# Ideamart_NB-IoT_DevBoard_v1_1.net
KiCad netlist of a schematic drawn in EAGLE
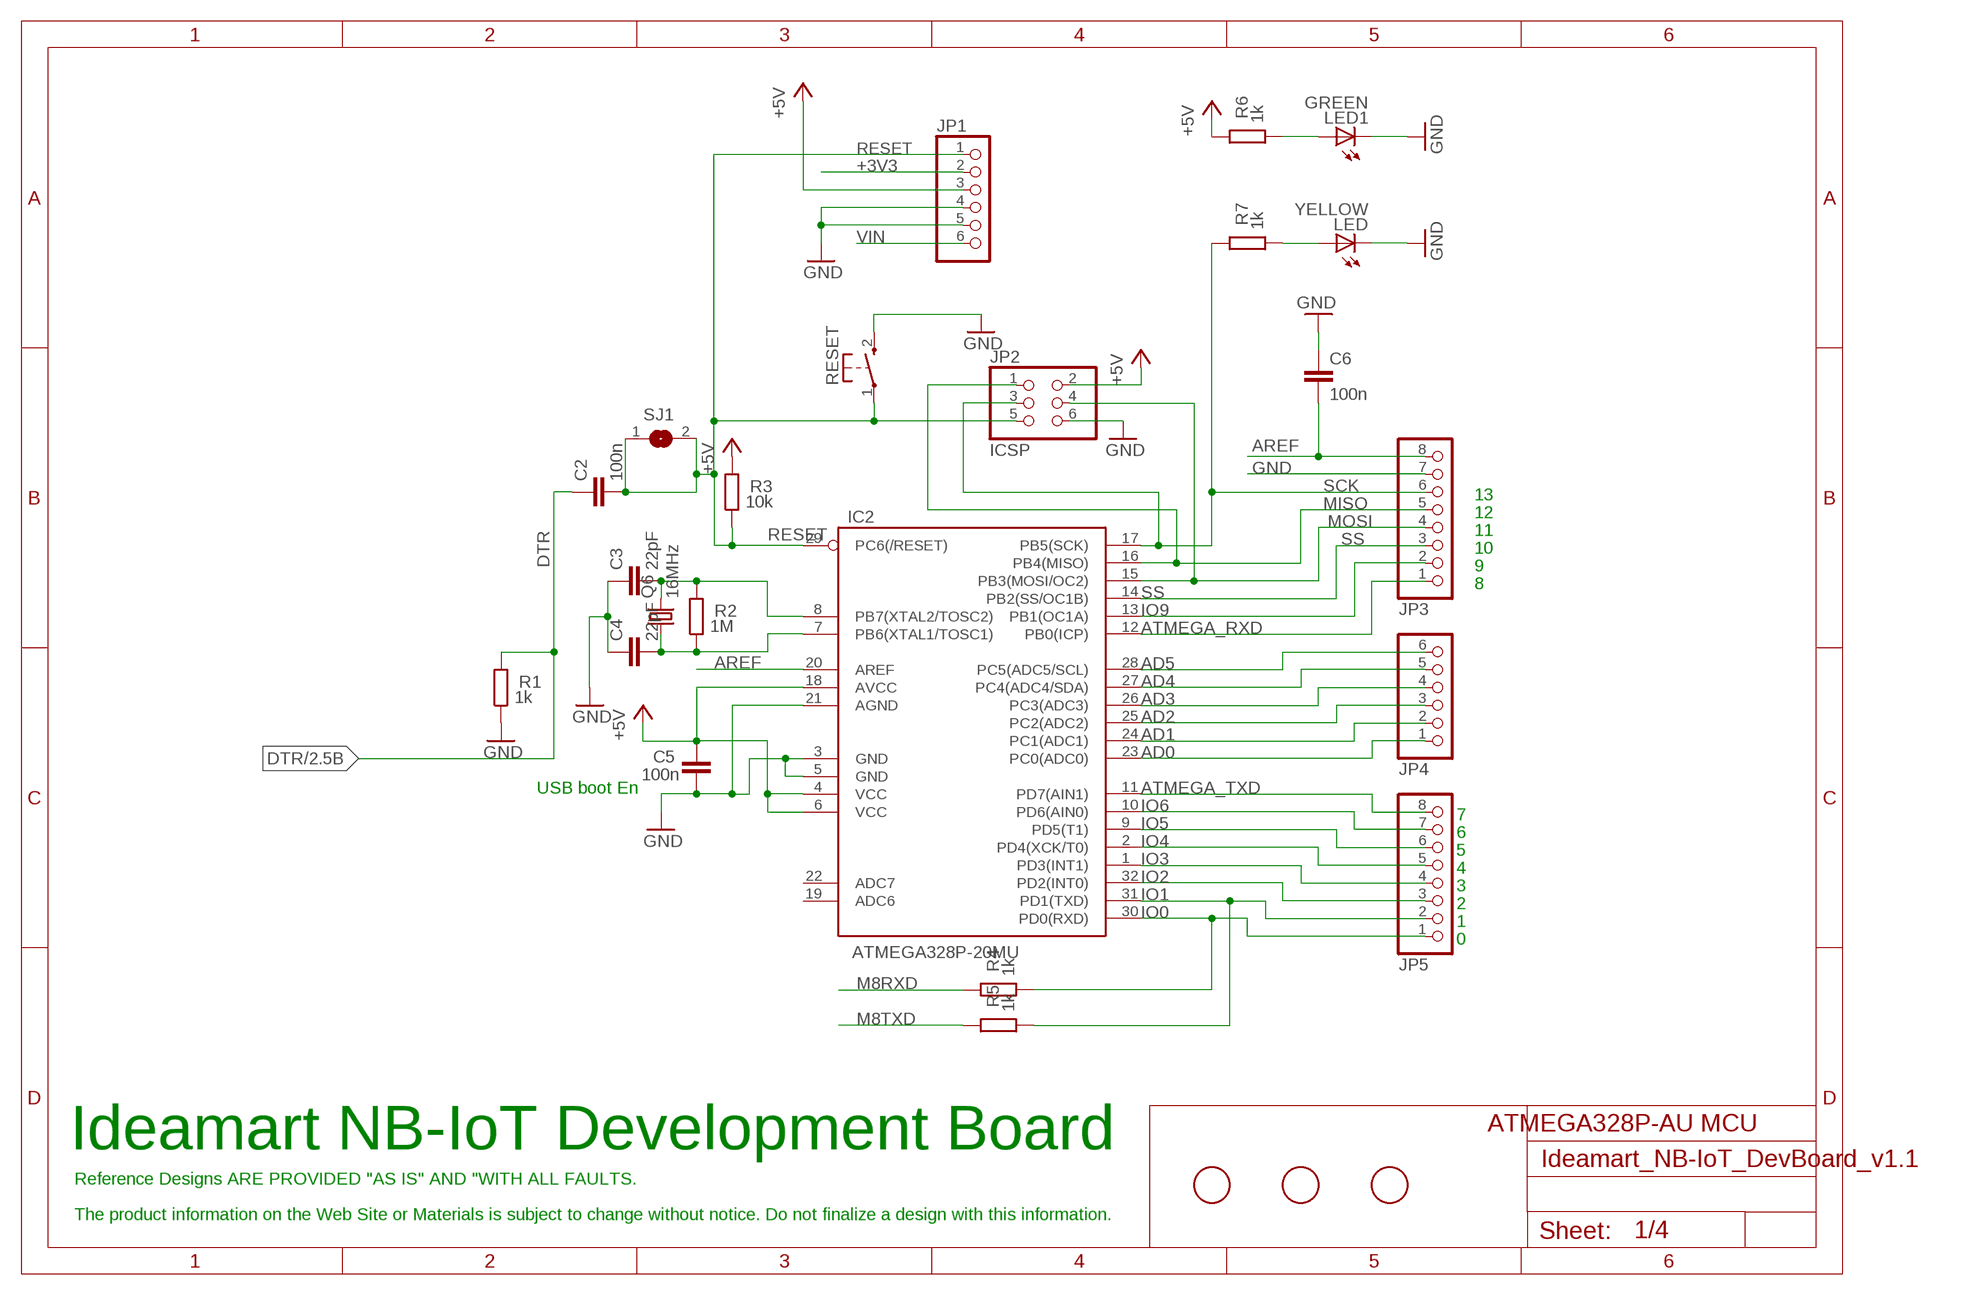
[diagram p0: schematic, sheet 1]
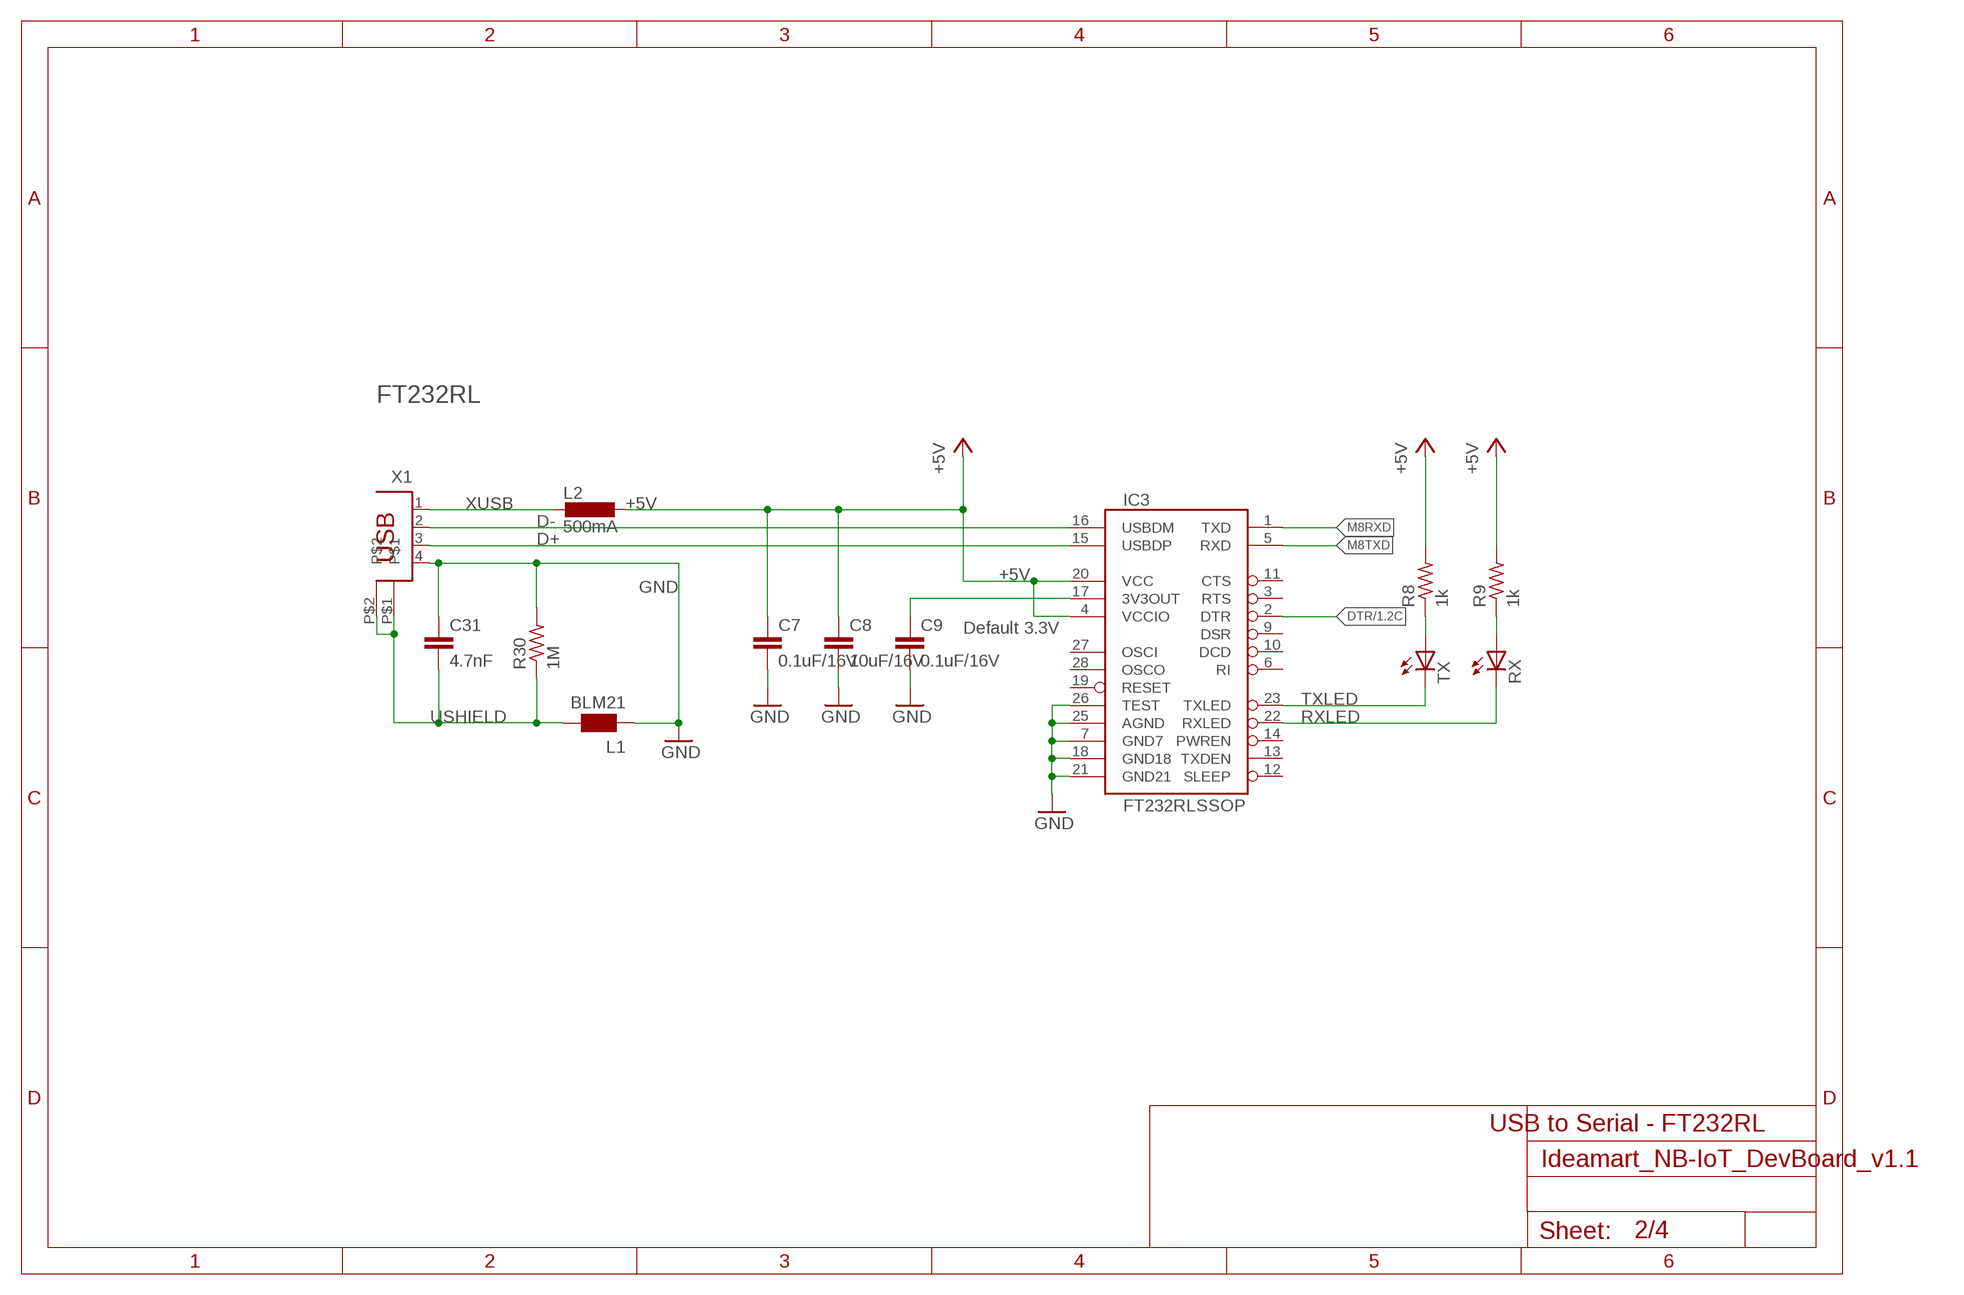
[diagram p1: schematic, sheet 2]
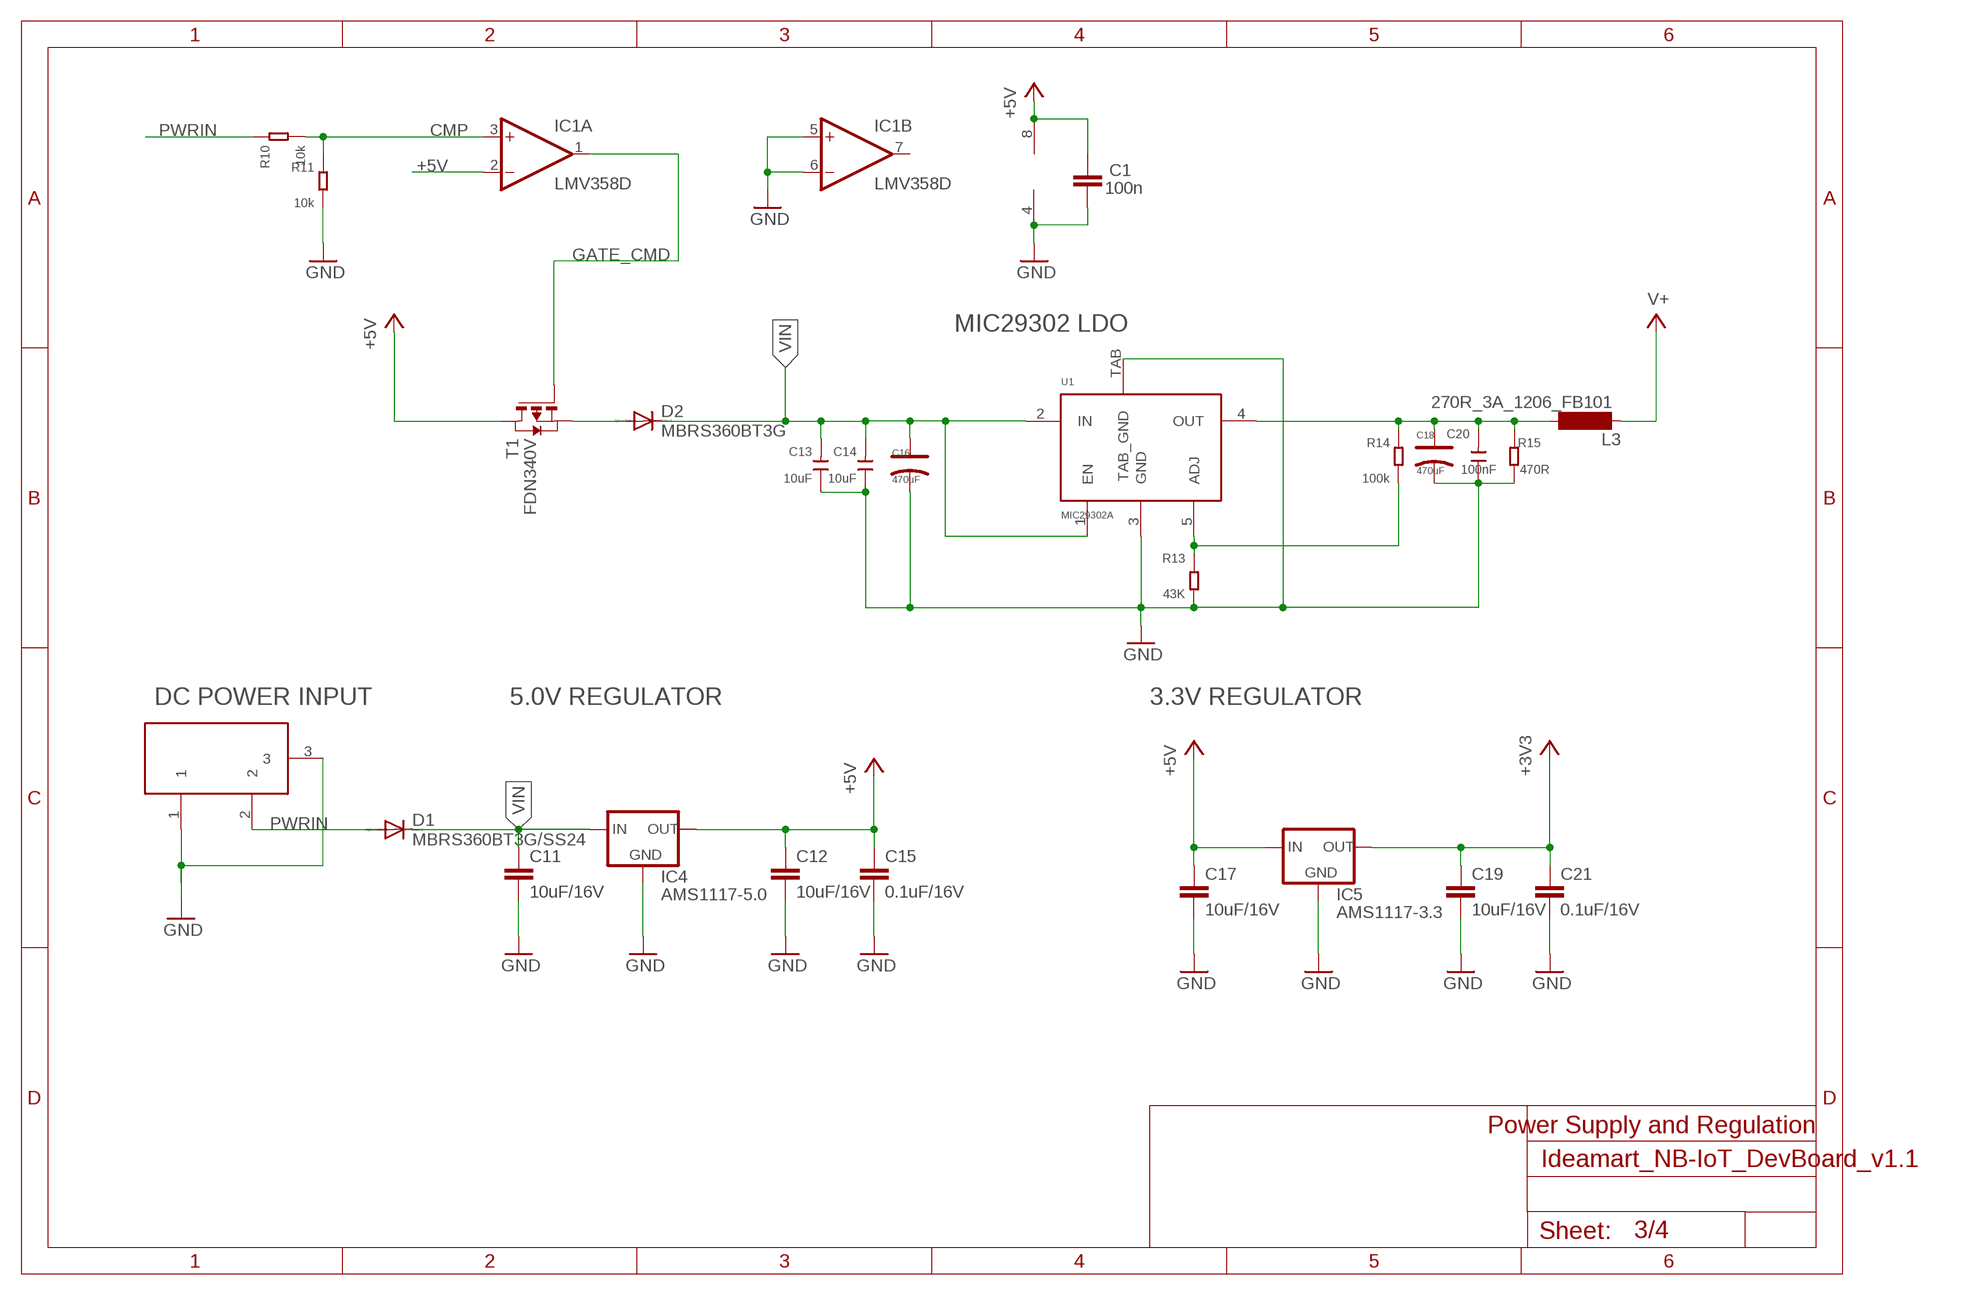
[diagram p2: schematic, sheet 3]
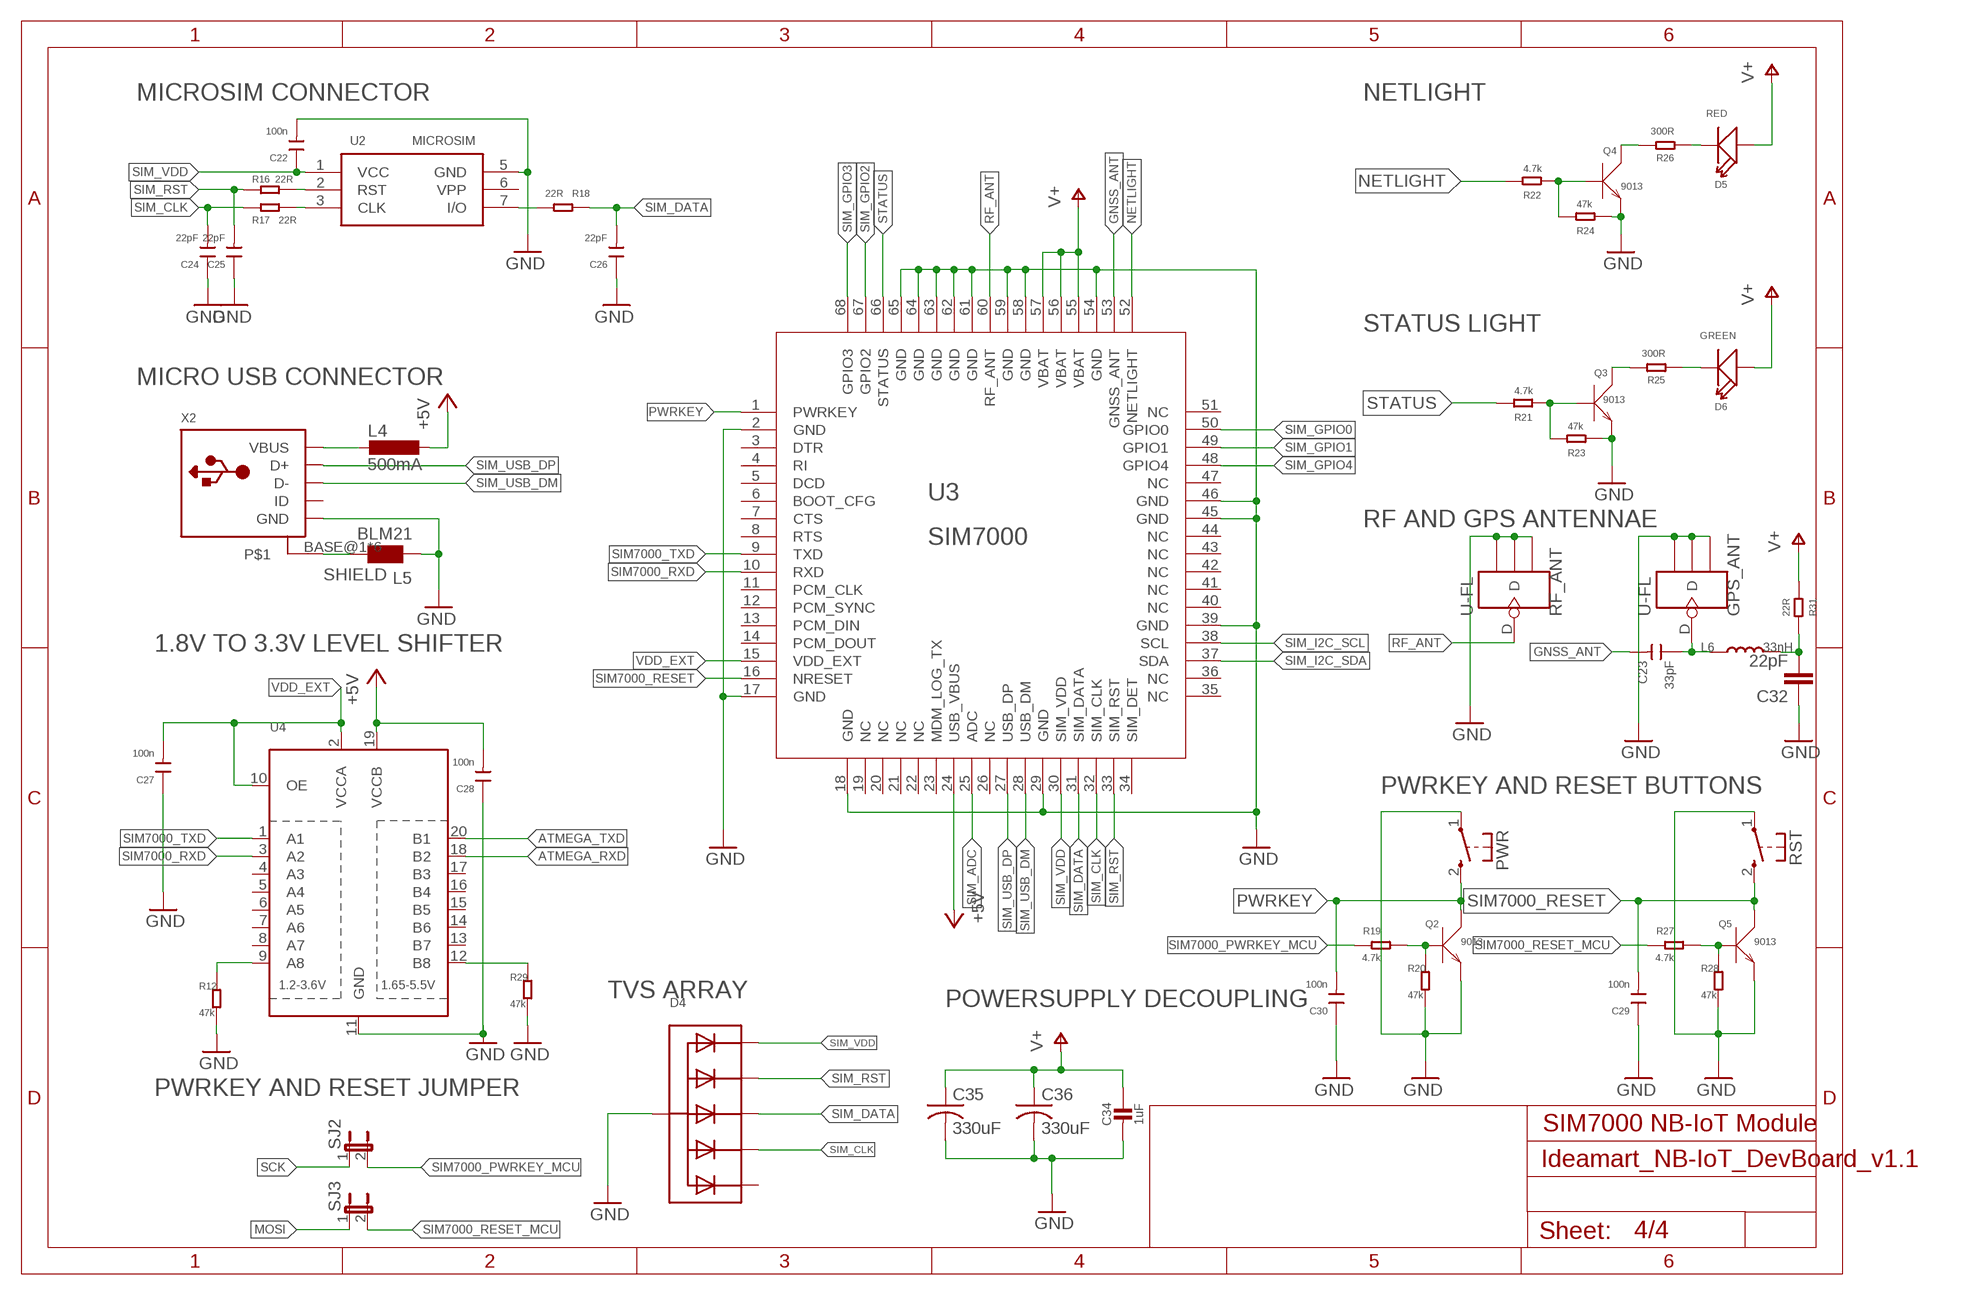
[diagram p3: schematic, sheet 4]

(export (version "E")
  (design (tool "Eeschema 10.0.6"))
  (components
    (comp (ref "C22")
      (value "100n")
      (footprint "eagle-import:0805")
      (libsource (lib "eagle-import") (part "C-0805"))
    )
    (comp (ref "C23")
      (value "33pF")
      (footprint "eagle-import:0805")
      (libsource (lib "eagle-import") (part "C-0805"))
    )
    (comp (ref "C24")
      (value "22pF")
      (footprint "eagle-import:0805")
      (libsource (lib "eagle-import") (part "C-0805"))
    )
    (comp (ref "C25")
      (value "22pF")
      (footprint "eagle-import:0805")
      (libsource (lib "eagle-import") (part "C-0805"))
    )
    (comp (ref "C26")
      (value "22pF")
      (footprint "eagle-import:0805")
      (libsource (lib "eagle-import") (part "C-0805"))
    )
    (comp (ref "C27")
      (value "100n")
      (footprint "eagle-import:0805")
      (libsource (lib "eagle-import") (part "C-0805"))
    )
    (comp (ref "C28")
      (value "100n")
      (footprint "eagle-import:0805")
      (libsource (lib "eagle-import") (part "C-0805"))
    )
    (comp (ref "C29")
      (value "100n")
      (footprint "eagle-import:0805")
      (libsource (lib "eagle-import") (part "C-0805"))
    )
    (comp (ref "C30")
      (value "100n")
      (footprint "eagle-import:0805")
      (libsource (lib "eagle-import") (part "C-0805"))
    )
    (comp (ref "C32")
      (value "22pF")
      (footprint "eagle-import:C0805")
      (libsource (lib "eagle-import") (part "C-EUC0805"))
    )
    (comp (ref "C34")
      (value "1uF")
      (footprint "eagle-import:_0805")
      (libsource (lib "eagle-import") (part "CAP_CERAMIC_0805"))
    )
    (comp (ref "C35")
      (value "330uF")
      (footprint "eagle-import:C1210")
      (libsource (lib "eagle-import") (part "C-USC1210"))
    )
    (comp (ref "C36")
      (value "330uF")
      (footprint "eagle-import:C1210")
      (libsource (lib "eagle-import") (part "C-USC1210"))
    )
    (comp (ref "D4")
      (value "TVSARRAY_5LANE")
      (footprint "eagle-import:SOT363")
      (libsource (lib "eagle-import") (part "TVSARRAY_5LANE"))
    )
    (comp (ref "D5")
      (value "RED")
      (footprint "eagle-import:LED-0805")
      (libsource (lib "eagle-import") (part "LED'0805'"))
    )
    (comp (ref "D6")
      (value "GREEN")
      (footprint "eagle-import:LED-0805")
      (libsource (lib "eagle-import") (part "LED'0805'"))
    )
    (comp (ref "GPS_ANT")
      (value "U-FL")
      (footprint "eagle-import:4P-U-FL")
      (libsource (lib "eagle-import") (part "ANTENNA-U-FL"))
    )
    (comp (ref "L4")
      (value "500mA")
      (footprint "eagle-import:L1812")
      (libsource (lib "eagle-import") (part "L-EUL1812"))
    )
    (comp (ref "L5")
      (value "BLM21")
      (footprint "eagle-import:0805")
      (libsource (lib "eagle-import") (part "WE-CBF_0805"))
    )
    (comp (ref "L6")
      (value "33nH")
      (footprint "eagle-import:L0805")
      (libsource (lib "eagle-import") (part "L0805"))
    )
    (comp (ref "PWR")
      (value "KSS-2EG4430")
      (footprint "eagle-import:KSS-2EG4430")
      (libsource (lib "eagle-import") (part "KSS-2EG4430"))
    )
    (comp (ref "Q2")
      (value "9013")
      (footprint "eagle-import:SOT23")
      (libsource (lib "eagle-import") (part "TRANSISTOR-NPN-SOT23"))
    )
    (comp (ref "Q3")
      (value "9013")
      (footprint "eagle-import:SOT23")
      (libsource (lib "eagle-import") (part "TRANSISTOR-NPN-SOT23"))
    )
    (comp (ref "Q4")
      (value "9013")
      (footprint "eagle-import:SOT23")
      (libsource (lib "eagle-import") (part "TRANSISTOR-NPN-SOT23"))
    )
    (comp (ref "Q5")
      (value "9013")
      (footprint "eagle-import:SOT23")
      (libsource (lib "eagle-import") (part "TRANSISTOR-NPN-SOT23"))
    )
    (comp (ref "R12")
      (value "47k")
      (footprint "eagle-import:0805")
      (libsource (lib "eagle-import") (part "R-0805"))
    )
    (comp (ref "R16")
      (value "22R")
      (footprint "eagle-import:0805")
      (libsource (lib "eagle-import") (part "R-0805"))
    )
    (comp (ref "R17")
      (value "22R")
      (footprint "eagle-import:0805")
      (libsource (lib "eagle-import") (part "R-0805"))
    )
    (comp (ref "R18")
      (value "22R")
      (footprint "eagle-import:0805")
      (libsource (lib "eagle-import") (part "R-0805"))
    )
    (comp (ref "R19")
      (value "4.7k")
      (footprint "eagle-import:0805")
      (libsource (lib "eagle-import") (part "R-0805"))
    )
    (comp (ref "R20")
      (value "47k")
      (footprint "eagle-import:0805")
      (libsource (lib "eagle-import") (part "R-0805"))
    )
    (comp (ref "R21")
      (value "4.7k")
      (footprint "eagle-import:0805")
      (libsource (lib "eagle-import") (part "R-0805"))
    )
    (comp (ref "R22")
      (value "4.7k")
      (footprint "eagle-import:0805")
      (libsource (lib "eagle-import") (part "R-0805"))
    )
    (comp (ref "R23")
      (value "47k")
      (footprint "eagle-import:0805")
      (libsource (lib "eagle-import") (part "R-0805"))
    )
    (comp (ref "R24")
      (value "47k")
      (footprint "eagle-import:0805")
      (libsource (lib "eagle-import") (part "R-0805"))
    )
    (comp (ref "R25")
      (value "300R")
      (footprint "eagle-import:0805")
      (libsource (lib "eagle-import") (part "R-0805"))
    )
    (comp (ref "R26")
      (value "300R")
      (footprint "eagle-import:0805")
      (libsource (lib "eagle-import") (part "R-0805"))
    )
    (comp (ref "R27")
      (value "4.7k")
      (footprint "eagle-import:0805")
      (libsource (lib "eagle-import") (part "R-0805"))
    )
    (comp (ref "R28")
      (value "47k")
      (footprint "eagle-import:0805")
      (libsource (lib "eagle-import") (part "R-0805"))
    )
    (comp (ref "R29")
      (value "47k")
      (footprint "eagle-import:0805")
      (libsource (lib "eagle-import") (part "R-0805"))
    )
    (comp (ref "R31")
      (value "22R")
      (footprint "eagle-import:0805")
      (libsource (lib "eagle-import") (part "R-0805"))
    )
    (comp (ref "RF_ANT")
      (value "U-FL")
      (footprint "eagle-import:4P-U-FL")
      (libsource (lib "eagle-import") (part "ANTENNA-U-FL"))
    )
    (comp (ref "RST")
      (value "KSS-2EG4430")
      (footprint "eagle-import:KSS-2EG4430")
      (libsource (lib "eagle-import") (part "KSS-2EG4430"))
    )
    (comp (ref "SJ2")
      (value "SPARKFUN-PASSIVES_JUMPER-PTH-2-NC")
      (footprint "eagle-import:SPARKFUN-PASSIVES_PTH-JUMPER-NC_BOTTOM_NO_SILK")
      (libsource (lib "eagle-import") (part "SPARKFUN-PASSIVES_JUMPER-PTH-2-NC"))
    )
    (comp (ref "SJ3")
      (value "SPARKFUN-PASSIVES_JUMPER-PTH-2-NC")
      (footprint "eagle-import:SPARKFUN-PASSIVES_PTH-JUMPER-NC_BOTTOM_NO_SILK")
      (libsource (lib "eagle-import") (part "SPARKFUN-PASSIVES_JUMPER-PTH-2-NC"))
    )
    (comp (ref "U2")
      (value "MICROSIM")
      (footprint "eagle-import:MICROSIM")
      (libsource (lib "eagle-import") (part "MICROSIM"))
    )
    (comp (ref "U3")
      (value "SIM7000")
      (footprint "eagle-import:SIM7000")
      (libsource (lib "eagle-import") (part "SIM7000"))
    )
    (comp (ref "U4")
      (value "TXB0108PWR")
      (footprint "eagle-import:TSSOP20")
      (libsource (lib "eagle-import") (part "TXB0108PWR"))
    )
    (comp (ref "X2")
      (value "USB_MICRO_20329_V2")
      (footprint "eagle-import:4UCONN_20329_V2")
      (libsource (lib "eagle-import") (part "USB_MICRO_20329_V2"))
    )
    (comp (ref "C2")
      (value "100n")
      (footprint "eagle-import:C0805")
      (libsource (lib "eagle-import") (part "C-EUC0805"))
    )
    (comp (ref "C3")
      (value "22pF")
      (footprint "eagle-import:C0805")
      (libsource (lib "eagle-import") (part "C-EUC0805"))
    )
    (comp (ref "C4")
      (value "22pF")
      (footprint "eagle-import:C0805")
      (libsource (lib "eagle-import") (part "C-EUC0805"))
    )
    (comp (ref "C5")
      (value "100n")
      (footprint "eagle-import:C0805")
      (libsource (lib "eagle-import") (part "C-EUC0805"))
    )
    (comp (ref "C6")
      (value "100n")
      (footprint "eagle-import:C0805")
      (libsource (lib "eagle-import") (part "C-EUC0805"))
    )
    (comp (ref "IC2")
      (value "ATMEGA328P-20MU")
      (footprint "eagle-import:TQFP32-08")
      (libsource (lib "eagle-import") (part "MEGA8-AI"))
    )
    (comp (ref "JP1")
      (value "PINHD-1X6")
      (footprint "eagle-import:1X06")
      (libsource (lib "eagle-import") (part "PINHD-1X6"))
    )
    (comp (ref "JP2")
      (value "ICSP")
      (footprint "eagle-import:2X03")
      (libsource (lib "eagle-import") (part "PINHD-2X3"))
    )
    (comp (ref "JP3")
      (value "PINHD-1X8")
      (footprint "eagle-import:1X08")
      (libsource (lib "eagle-import") (part "PINHD-1X8"))
    )
    (comp (ref "JP4")
      (value "PINHD-1X6")
      (footprint "eagle-import:1X06")
      (libsource (lib "eagle-import") (part "PINHD-1X6"))
    )
    (comp (ref "JP5")
      (value "PINHD-1X8")
      (footprint "eagle-import:1X08")
      (libsource (lib "eagle-import") (part "PINHD-1X8"))
    )
    (comp (ref "LED")
      (value "YELLOW")
      (footprint "eagle-import:CHIP-LED0805")
      (libsource (lib "eagle-import") (part "LEDCHIP-LED0805"))
    )
    (comp (ref "LED1")
      (value "GREEN")
      (footprint "eagle-import:CHIP-LED0805")
      (libsource (lib "eagle-import") (part "LEDCHIP-LED0805"))
    )
    (comp (ref "M1")
      (value "FIDUCIALMOUNT")
      (footprint "eagle-import:FIDUCIA-MOUNT")
      (libsource (lib "eagle-import") (part "FIDUCIALMOUNT"))
    )
    (comp (ref "M2")
      (value "FIDUCIALMOUNT")
      (footprint "eagle-import:FIDUCIA-MOUNT")
      (libsource (lib "eagle-import") (part "FIDUCIALMOUNT"))
    )
    (comp (ref "M3")
      (value "FIDUCIALMOUNT")
      (footprint "eagle-import:FIDUCIA-MOUNT")
      (libsource (lib "eagle-import") (part "FIDUCIALMOUNT"))
    )
    (comp (ref "Q6")
      (value "16MHz")
      (footprint "eagle-import:CTS406")
      (libsource (lib "eagle-import") (part "CRYSTALCTS406"))
    )
    (comp (ref "R1")
      (value "1k")
      (footprint "eagle-import:R0805")
      (libsource (lib "eagle-import") (part "R-EU_R0805"))
    )
    (comp (ref "R2")
      (value "1M")
      (footprint "eagle-import:R0805")
      (libsource (lib "eagle-import") (part "R-EU_R0805"))
    )
    (comp (ref "R3")
      (value "10k")
      (footprint "eagle-import:R0805")
      (libsource (lib "eagle-import") (part "R-EU_R0805"))
    )
    (comp (ref "R4")
      (value "1k")
      (footprint "eagle-import:R0805")
      (libsource (lib "eagle-import") (part "R-EU_R0805"))
    )
    (comp (ref "R5")
      (value "1k")
      (footprint "eagle-import:R0805")
      (libsource (lib "eagle-import") (part "R-EU_R0805"))
    )
    (comp (ref "R6")
      (value "1k")
      (footprint "eagle-import:R0805")
      (libsource (lib "eagle-import") (part "R-EU_R0805"))
    )
    (comp (ref "R7")
      (value "1k")
      (footprint "eagle-import:R0805")
      (libsource (lib "eagle-import") (part "R-EU_R0805"))
    )
    (comp (ref "RESET")
      (value "KSS-2EG4430")
      (footprint "eagle-import:KSS-2EG4430")
      (libsource (lib "eagle-import") (part "KSS-2EG4430"))
    )
    (comp (ref "SJ1") (value "SJ") (footprint "eagle-import:SJ") (libsource (lib "eagle-import") (part "SJ")))
    (comp (ref "C7")
      (value "0.1uF/16V")
      (footprint "eagle-import:C0805K")
      (libsource (lib "eagle-import") (part "rcl_C-EUC0805K"))
    )
    (comp (ref "C8")
      (value "10uF/16V")
      (footprint "eagle-import:C0805K")
      (libsource (lib "eagle-import") (part "rcl_C-EUC0805K"))
    )
    (comp (ref "C9")
      (value "0.1uF/16V")
      (footprint "eagle-import:C0805K")
      (libsource (lib "eagle-import") (part "rcl_C-EUC0805K"))
    )
    (comp (ref "C31")
      (value "4.7nF")
      (footprint "eagle-import:C0805K")
      (libsource (lib "eagle-import") (part "rcl_C-EUC0805K"))
    )
    (comp (ref "IC3")
      (value "FT232RLSSOP")
      (footprint "eagle-import:SSOP28DB")
      (libsource (lib "eagle-import") (part "FT232RLSSOP"))
    )
    (comp (ref "L1")
      (value "BLM21")
      (footprint "eagle-import:0805")
      (libsource (lib "eagle-import") (part "WE-CBF_0805"))
    )
    (comp (ref "L2")
      (value "500mA")
      (footprint "eagle-import:L1812")
      (libsource (lib "eagle-import") (part "L-EUL1812"))
    )
    (comp (ref "R8")
      (value "1k")
      (footprint "eagle-import:M0805")
      (libsource (lib "eagle-import") (part "R-US_M0805"))
    )
    (comp (ref "R9")
      (value "1k")
      (footprint "eagle-import:M0805")
      (libsource (lib "eagle-import") (part "R-US_M0805"))
    )
    (comp (ref "R30")
      (value "1M")
      (footprint "eagle-import:M0805")
      (libsource (lib "eagle-import") (part "R-US_M0805"))
    )
    (comp (ref "RX")
      (value "LEDCHIP-LED0805")
      (footprint "eagle-import:CHIP-LED0805")
      (libsource (lib "eagle-import") (part "LEDCHIP-LED0805"))
    )
    (comp (ref "TX")
      (value "LEDCHIP-LED0805")
      (footprint "eagle-import:CHIP-LED0805")
      (libsource (lib "eagle-import") (part "LEDCHIP-LED0805"))
    )
    (comp (ref "X1")
      (value "PN61729")
      (footprint "eagle-import:PN61729")
      (libsource (lib "eagle-import") (part "PN61729"))
    )
    (comp (ref "C1")
      (value "100n")
      (footprint "eagle-import:C0805")
      (libsource (lib "eagle-import") (part "C-EUC0805"))
    )
    (comp (ref "C11")
      (value "10uF/16V")
      (footprint "eagle-import:C0805K")
      (libsource (lib "eagle-import") (part "rcl_C-EUC0805K"))
    )
    (comp (ref "C12")
      (value "10uF/16V")
      (footprint "eagle-import:C0805K")
      (libsource (lib "eagle-import") (part "rcl_C-EUC0805K"))
    )
    (comp (ref "C13")
      (value "10uF")
      (footprint "eagle-import:0805")
      (libsource (lib "eagle-import") (part "C-0805"))
    )
    (comp (ref "C14")
      (value "10uF")
      (footprint "eagle-import:0805")
      (libsource (lib "eagle-import") (part "C-0805"))
    )
    (comp (ref "C15")
      (value "0.1uF/16V")
      (footprint "eagle-import:C0805K")
      (libsource (lib "eagle-import") (part "rcl_C-EUC0805K"))
    )
    (comp (ref "C16")
      (value "470uF")
      (footprint "eagle-import:AVX_D")
      (libsource (lib "eagle-import") (part "006-CAP_AVX_D"))
    )
    (comp (ref "C17")
      (value "10uF/16V")
      (footprint "eagle-import:C0805K")
      (libsource (lib "eagle-import") (part "rcl_C-EUC0805K"))
    )
    (comp (ref "C18")
      (value "470uF")
      (footprint "eagle-import:AVX_D")
      (libsource (lib "eagle-import") (part "006-CAP_AVX_D"))
    )
    (comp (ref "C19")
      (value "10uF/16V")
      (footprint "eagle-import:C0805K")
      (libsource (lib "eagle-import") (part "rcl_C-EUC0805K"))
    )
    (comp (ref "C20")
      (value "100nF")
      (footprint "eagle-import:0805")
      (libsource (lib "eagle-import") (part "C-0805"))
    )
    (comp (ref "C21")
      (value "0.1uF/16V")
      (footprint "eagle-import:C0805K")
      (libsource (lib "eagle-import") (part "rcl_C-EUC0805K"))
    )
    (comp (ref "D1")
      (value "MBRS360BT3G/SS24")
      (footprint "eagle-import:SMB")
      (libsource (lib "eagle-import") (part "DIODE-SMB"))
    )
    (comp (ref "D2")
      (value "MBRS360BT3G")
      (footprint "eagle-import:SMB")
      (libsource (lib "eagle-import") (part "DIODE-SMB"))
    )
    (comp (ref "IC1")
      (value "LMV358D")
      (footprint "eagle-import:SO08")
      (libsource (lib "eagle-import") (part "LM358D"))
    )
    (comp (ref "IC4")
      (value "AMS1117-5.0")
      (footprint "eagle-import:SOT223")
      (libsource (lib "eagle-import") (part "LM1117"))
    )
    (comp (ref "IC5")
      (value "AMS1117-3.3")
      (footprint "eagle-import:SOT223")
      (libsource (lib "eagle-import") (part "LM1117"))
    )
    (comp (ref "L3")
      (value "270R_3A_1206_FB101")
      (footprint "eagle-import:SM-1206")
      (libsource (lib "eagle-import") (part "SM-1206"))
    )
    (comp (ref "R10")
      (value "10k")
      (footprint "eagle-import:0805")
      (libsource (lib "eagle-import") (part "R-0805"))
    )
    (comp (ref "R11")
      (value "10k")
      (footprint "eagle-import:0805")
      (libsource (lib "eagle-import") (part "R-0805"))
    )
    (comp (ref "R13")
      (value "43K")
      (footprint "eagle-import:0805")
      (libsource (lib "eagle-import") (part "R-0805"))
    )
    (comp (ref "R14")
      (value "100k")
      (footprint "eagle-import:0805")
      (libsource (lib "eagle-import") (part "R-0805"))
    )
    (comp (ref "R15")
      (value "470R")
      (footprint "eagle-import:0805")
      (libsource (lib "eagle-import") (part "R-0805"))
    )
    (comp (ref "T1")
      (value "FDN340V")
      (footprint "eagle-import:SOT-23")
      (libsource (lib "eagle-import") (part "PMOSSOT23"))
    )
    (comp (ref "U1")
      (value "MIC29302A")
      (footprint "eagle-import:TO-263A")
      (libsource (lib "eagle-import") (part "MIC29302A"))
    )
    (comp (ref "X3")
      (value "DC21MMX")
      (footprint "eagle-import:DC-21MM")
      (libsource (lib "eagle-import") (part "DC21MMX"))
    )
  )
  (nets
    (net (code "1") (name "+3V3") (class "Default")
      (node (ref "C19") (pin "1") (pinfunction "1_1") (pintype "passive"))
      (node (ref "C21") (pin "1") (pinfunction "1_1") (pintype "passive"))
      (node (ref "IC5") (pin "2") (pinfunction "OUT_2") (pintype "passive"))
      (node (ref "JP1") (pin "2") (pinfunction "2_2") (pintype "passive"))
    )
    (net (code "2") (name "+5V") (class "Default")
      (node (ref "C1") (pin "2") (pinfunction "2_2") (pintype "passive"))
      (node (ref "C12") (pin "1") (pinfunction "1_1") (pintype "passive"))
      (node (ref "C15") (pin "1") (pinfunction "1_1") (pintype "passive"))
      (node (ref "C17") (pin "1") (pinfunction "1_1") (pintype "passive"))
      (node (ref "C28") (pin "2") (pinfunction "2_2") (pintype "passive"))
      (node (ref "C5") (pin "2") (pinfunction "2_2") (pintype "passive"))
      (node (ref "C7") (pin "1") (pinfunction "1_1") (pintype "passive"))
      (node (ref "C8") (pin "1") (pinfunction "1_1") (pintype "passive"))
      (node (ref "IC1") (pin "2") (pinfunction "-IN_2") (pintype "input"))
      (node (ref "IC1") (pin "8") (pinfunction "V+_8") (pintype "power_in"))
      (node (ref "IC2") (pin "18") (pinfunction "AVCC_18") (pintype "bidirectional"))
      (node (ref "IC2") (pin "4") (pinfunction "VCC_4") (pintype "bidirectional"))
      (node (ref "IC2") (pin "6") (pinfunction "VCC_6") (pintype "bidirectional"))
      (node (ref "IC3") (pin "20") (pinfunction "VCC_20") (pintype "power_in"))
      (node (ref "IC3") (pin "4") (pinfunction "VCCIO_4") (pintype "power_in"))
      (node (ref "IC4") (pin "2") (pinfunction "OUT_2") (pintype "passive"))
      (node (ref "IC5") (pin "3") (pinfunction "IN_3") (pintype "input"))
      (node (ref "JP1") (pin "3") (pinfunction "3_3") (pintype "passive"))
      (node (ref "JP2") (pin "2") (pinfunction "2_2") (pintype "passive"))
      (node (ref "L2") (pin "1") (pinfunction "1_1") (pintype "passive"))
      (node (ref "L4") (pin "1") (pinfunction "1_1") (pintype "passive"))
      (node (ref "R3") (pin "2") (pinfunction "2_2") (pintype "passive"))
      (node (ref "R6") (pin "2") (pinfunction "2_2") (pintype "passive"))
      (node (ref "R8") (pin "2") (pinfunction "2_2") (pintype "passive"))
      (node (ref "R9") (pin "2") (pinfunction "2_2") (pintype "passive"))
      (node (ref "T1") (pin "1") (pinfunction "D_1") (pintype "passive"))
      (node (ref "U3") (pin "24") (pinfunction "USB_VBUS_24") (pintype "output"))
      (node (ref "U4") (pin "19") (pinfunction "VCCB_19") (pintype "bidirectional"))
    )
    (net (code "3") (name "AD0") (class "Default")
      (node (ref "IC2") (pin "23") (pinfunction "PC0(ADC0)_23") (pintype "bidirectional"))
      (node (ref "JP4") (pin "1") (pinfunction "1_1") (pintype "passive"))
    )
    (net (code "4") (name "AD1") (class "Default")
      (node (ref "IC2") (pin "24") (pinfunction "PC1(ADC1)_24") (pintype "bidirectional"))
      (node (ref "JP4") (pin "2") (pinfunction "2_2") (pintype "passive"))
    )
    (net (code "5") (name "AD2") (class "Default")
      (node (ref "IC2") (pin "25") (pinfunction "PC2(ADC2)_25") (pintype "bidirectional"))
      (node (ref "JP4") (pin "3") (pinfunction "3_3") (pintype "passive"))
    )
    (net (code "6") (name "AD3") (class "Default")
      (node (ref "IC2") (pin "26") (pinfunction "PC3(ADC3)_26") (pintype "bidirectional"))
      (node (ref "JP4") (pin "4") (pinfunction "4_4") (pintype "passive"))
    )
    (net (code "7") (name "AD4") (class "Default")
      (node (ref "IC2") (pin "27") (pinfunction "PC4(ADC4/SDA)_27") (pintype "bidirectional"))
      (node (ref "JP4") (pin "5") (pinfunction "5_5") (pintype "passive"))
    )
    (net (code "8") (name "AD5") (class "Default")
      (node (ref "IC2") (pin "28") (pinfunction "PC5(ADC5/SCL)_28") (pintype "bidirectional"))
      (node (ref "JP4") (pin "6") (pinfunction "6_6") (pintype "passive"))
    )
    (net (code "9") (name "AREF") (class "Default")
      (node (ref "C6") (pin "2") (pinfunction "2_2") (pintype "passive"))
      (node (ref "IC2") (pin "20") (pinfunction "AREF_20") (pintype "bidirectional"))
      (node (ref "JP3") (pin "8") (pinfunction "8_8") (pintype "passive"))
    )
    (net (code "10") (name "ATMEGA_RXD") (class "Default")
      (node (ref "IC2") (pin "12") (pinfunction "PB0(ICP)_12") (pintype "bidirectional"))
      (node (ref "JP3") (pin "1") (pinfunction "1_1") (pintype "passive"))
      (node (ref "U4") (pin "18") (pinfunction "B2_18") (pintype "bidirectional"))
    )
    (net (code "11") (name "ATMEGA_TXD") (class "Default")
      (node (ref "IC2") (pin "11") (pinfunction "PD7(AIN1)_11") (pintype "bidirectional"))
      (node (ref "JP5") (pin "8") (pinfunction "8_8") (pintype "passive"))
      (node (ref "U4") (pin "20") (pinfunction "B1_20") (pintype "bidirectional"))
    )
    (net (code "12") (name "CMP") (class "Default")
      (node (ref "IC1") (pin "3") (pinfunction "+IN_3") (pintype "input"))
      (node (ref "R10") (pin "1") (pinfunction "1_1") (pintype "passive"))
      (node (ref "R11") (pin "2") (pinfunction "2_2") (pintype "passive"))
    )
    (net (code "13") (name "D+") (class "Default")
      (node (ref "IC3") (pin "15") (pinfunction "USBDP_15") (pintype "bidirectional"))
      (node (ref "X1") (pin "3") (pinfunction "3_3") (pintype "bidirectional"))
    )
    (net (code "14") (name "D-") (class "Default")
      (node (ref "IC3") (pin "16") (pinfunction "USBDM_16") (pintype "bidirectional"))
      (node (ref "X1") (pin "2") (pinfunction "2_2") (pintype "bidirectional"))
    )
    (net (code "15") (name "DTR") (class "Default")
      (node (ref "C2") (pin "1") (pinfunction "1_1") (pintype "passive"))
      (node (ref "IC3") (pin "2") (pinfunction "DTR_2") (pintype "output"))
      (node (ref "R1") (pin "2") (pinfunction "2_2") (pintype "passive"))
    )
    (net (code "16") (name "GATE_CMD") (class "Default")
      (node (ref "IC1") (pin "1") (pinfunction "OUT_1") (pintype "output"))
      (node (ref "T1") (pin "3") (pinfunction "G_3") (pintype "passive"))
    )
    (net (code "17") (name "GND") (class "Default")
      (node (ref "C1") (pin "1") (pinfunction "1_1") (pintype "passive"))
      (node (ref "C11") (pin "2") (pinfunction "2_2") (pintype "passive"))
      (node (ref "C12") (pin "2") (pinfunction "2_2") (pintype "passive"))
      (node (ref "C13") (pin "1") (pinfunction "1_1") (pintype "passive"))
      (node (ref "C14") (pin "1") (pinfunction "1_1") (pintype "passive"))
      (node (ref "C15") (pin "2") (pinfunction "2_2") (pintype "passive"))
      (node (ref "C16") (pin "-") (pinfunction "-_-") (pintype "passive"))
      (node (ref "C17") (pin "2") (pinfunction "2_2") (pintype "passive"))
      (node (ref "C18") (pin "-") (pinfunction "-_-") (pintype "passive"))
      (node (ref "C19") (pin "2") (pinfunction "2_2") (pintype "passive"))
      (node (ref "C20") (pin "1") (pinfunction "1_1") (pintype "passive"))
      (node (ref "C21") (pin "2") (pinfunction "2_2") (pintype "passive"))
      (node (ref "C22") (pin "2") (pinfunction "2_2") (pintype "passive"))
      (node (ref "C24") (pin "1") (pinfunction "1_1") (pintype "passive"))
      (node (ref "C25") (pin "1") (pinfunction "1_1") (pintype "passive"))
      (node (ref "C26") (pin "1") (pinfunction "1_1") (pintype "passive"))
      (node (ref "C27") (pin "1") (pinfunction "1_1") (pintype "passive"))
      (node (ref "C28") (pin "1") (pinfunction "1_1") (pintype "passive"))
      (node (ref "C29") (pin "1") (pinfunction "1_1") (pintype "passive"))
      (node (ref "C3") (pin "1") (pinfunction "1_1") (pintype "passive"))
      (node (ref "C30") (pin "1") (pinfunction "1_1") (pintype "passive"))
      (node (ref "C31") (pin "1") (pinfunction "1_1") (pintype "passive"))
      (node (ref "C32") (pin "1") (pinfunction "1_1") (pintype "passive"))
      (node (ref "C34") (pin "2") (pinfunction "2_2") (pintype "passive"))
      (node (ref "C35") (pin "2") (pinfunction "2_2") (pintype "passive"))
      (node (ref "C36") (pin "2") (pinfunction "2_2") (pintype "passive"))
      (node (ref "C4") (pin "1") (pinfunction "1_1") (pintype "passive"))
      (node (ref "C5") (pin "1") (pinfunction "1_1") (pintype "passive"))
      (node (ref "C6") (pin "1") (pinfunction "1_1") (pintype "passive"))
      (node (ref "C7") (pin "2") (pinfunction "2_2") (pintype "passive"))
      (node (ref "C8") (pin "2") (pinfunction "2_2") (pintype "passive"))
      (node (ref "C9") (pin "2") (pinfunction "2_2") (pintype "passive"))
      (node (ref "D4") (pin "2") (pinfunction "A_2") (pintype "passive"))
      (node (ref "GPS_ANT") (pin "GND1") (pinfunction "GND1_GND1") (pintype "bidirectional"))
      (node (ref "GPS_ANT") (pin "GND2") (pinfunction "GND2_GND2") (pintype "bidirectional"))
      (node (ref "GPS_ANT") (pin "GND3") (pinfunction "GND3_GND3") (pintype "bidirectional"))
      (node (ref "IC1") (pin "4") (pinfunction "V-_4") (pintype "power_in"))
      (node (ref "IC1") (pin "5") (pinfunction "+IN_5") (pintype "input"))
      (node (ref "IC1") (pin "6") (pinfunction "-IN_6") (pintype "input"))
      (node (ref "IC2") (pin "21") (pinfunction "AGND_21") (pintype "bidirectional"))
      (node (ref "IC2") (pin "3") (pinfunction "GND_3") (pintype "bidirectional"))
      (node (ref "IC2") (pin "5") (pinfunction "GND_5") (pintype "bidirectional"))
      (node (ref "IC3") (pin "18") (pinfunction "GND18_18") (pintype "power_in"))
      (node (ref "IC3") (pin "21") (pinfunction "GND21_21") (pintype "power_in"))
      (node (ref "IC3") (pin "25") (pinfunction "AGND_25") (pintype "power_in"))
      (node (ref "IC3") (pin "26") (pinfunction "TEST_26") (pintype "input"))
      (node (ref "IC3") (pin "7") (pinfunction "GND7_7") (pintype "power_in"))
      (node (ref "IC4") (pin "1") (pinfunction "GND_1") (pintype "input"))
      (node (ref "IC5") (pin "1") (pinfunction "GND_1") (pintype "input"))
      (node (ref "JP1") (pin "4") (pinfunction "4_4") (pintype "passive"))
      (node (ref "JP1") (pin "5") (pinfunction "5_5") (pintype "passive"))
      (node (ref "JP2") (pin "6") (pinfunction "6_6") (pintype "passive"))
      (node (ref "JP3") (pin "7") (pinfunction "7_7") (pintype "passive"))
      (node (ref "L1") (pin "1") (pinfunction "1_1") (pintype "passive"))
      (node (ref "L5") (pin "1") (pinfunction "1_1") (pintype "passive"))
      (node (ref "LED") (pin "C") (pinfunction "C_C") (pintype "passive"))
      (node (ref "LED1") (pin "C") (pinfunction "C_C") (pintype "passive"))
      (node (ref "PWR") (pin "1") (pinfunction "P_1") (pintype "passive"))
      (node (ref "Q2") (pin "2") (pinfunction "E_2") (pintype "passive"))
      (node (ref "Q3") (pin "2") (pinfunction "E_2") (pintype "passive"))
      (node (ref "Q4") (pin "2") (pinfunction "E_2") (pintype "passive"))
      (node (ref "Q5") (pin "2") (pinfunction "E_2") (pintype "passive"))
      (node (ref "R1") (pin "1") (pinfunction "1_1") (pintype "passive"))
      (node (ref "R11") (pin "1") (pinfunction "1_1") (pintype "passive"))
      (node (ref "R12") (pin "2") (pinfunction "2_2") (pintype "passive"))
      (node (ref "R13") (pin "1") (pinfunction "1_1") (pintype "passive"))
      (node (ref "R15") (pin "1") (pinfunction "1_1") (pintype "passive"))
      (node (ref "R20") (pin "2") (pinfunction "2_2") (pintype "passive"))
      (node (ref "R23") (pin "2") (pinfunction "2_2") (pintype "passive"))
      (node (ref "R24") (pin "2") (pinfunction "2_2") (pintype "passive"))
      (node (ref "R28") (pin "2") (pinfunction "2_2") (pintype "passive"))
      (node (ref "R29") (pin "2") (pinfunction "2_2") (pintype "passive"))
      (node (ref "R30") (pin "2") (pinfunction "2_2") (pintype "passive"))
      (node (ref "RESET") (pin "2") (pinfunction "S_2") (pintype "passive"))
      (node (ref "RF_ANT") (pin "GND1") (pinfunction "GND1_GND1") (pintype "bidirectional"))
      (node (ref "RF_ANT") (pin "GND2") (pinfunction "GND2_GND2") (pintype "bidirectional"))
      (node (ref "RF_ANT") (pin "GND3") (pinfunction "GND3_GND3") (pintype "bidirectional"))
      (node (ref "RST") (pin "1") (pinfunction "P_1") (pintype "passive"))
      (node (ref "U1") (pin "3") (pinfunction "GND_3") (pintype "bidirectional"))
      (node (ref "U1") (pin "TAB") (pinfunction "TAB_GND_TAB") (pintype "bidirectional"))
      (node (ref "U2") (pin "5") (pinfunction "GND_5") (pintype "bidirectional"))
      (node (ref "U3") (pin "17") (pinfunction "GND_17") (pintype "power_in"))
      (node (ref "U3") (pin "18") (pinfunction "GND_18") (pintype "power_in"))
      (node (ref "U3") (pin "2") (pinfunction "GND_2") (pintype "power_in"))
      (node (ref "U3") (pin "29") (pinfunction "GND_29") (pintype "power_in"))
      (node (ref "U3") (pin "39") (pinfunction "GND_39") (pintype "power_in"))
      (node (ref "U3") (pin "45") (pinfunction "GND_45") (pintype "power_in"))
      (node (ref "U3") (pin "46") (pinfunction "GND_46") (pintype "power_in"))
      (node (ref "U3") (pin "54") (pinfunction "GND_54") (pintype "power_in"))
      (node (ref "U3") (pin "58") (pinfunction "GND_58") (pintype "output"))
      (node (ref "U3") (pin "59") (pinfunction "GND_59") (pintype "bidirectional"))
      (node (ref "U3") (pin "61") (pinfunction "GND_61") (pintype "input"))
      (node (ref "U3") (pin "62") (pinfunction "GND_62") (pintype "output"))
      (node (ref "U3") (pin "63") (pinfunction "GND_63") (pintype "output"))
      (node (ref "U3") (pin "64") (pinfunction "GND_64") (pintype "input"))
      (node (ref "U3") (pin "65") (pinfunction "GND_65") (pintype "bidirectional"))
      (node (ref "U4") (pin "11") (pinfunction "GND_11") (pintype "bidirectional"))
      (node (ref "X1") (pin "4") (pinfunction "4_4") (pintype "bidirectional"))
      (node (ref "X2") (pin "GND") (pinfunction "GND_GND") (pintype "power_in"))
      (node (ref "X3") (pin "1") (pinfunction "1_1") (pintype "power_in"))
      (node (ref "X3") (pin "3") (pinfunction "3_3") (pintype "power_in"))
    )
    (net (code "18") (name "GNSS_ANT") (class "Default")
      (node (ref "C23") (pin "2") (pinfunction "2_2") (pintype "passive"))
      (node (ref "U3") (pin "53") (pinfunction "GNSS_ANT_53") (pintype "power_in"))
    )
    (net (code "19") (name "IO0") (class "Default")
      (node (ref "IC2") (pin "30") (pinfunction "PD0(RXD)_30") (pintype "bidirectional"))
      (node (ref "JP5") (pin "1") (pinfunction "1_1") (pintype "passive"))
      (node (ref "R4") (pin "1") (pinfunction "1_1") (pintype "passive"))
    )
    (net (code "20") (name "IO1") (class "Default")
      (node (ref "IC2") (pin "31") (pinfunction "PD1(TXD)_31") (pintype "bidirectional"))
      (node (ref "JP5") (pin "2") (pinfunction "2_2") (pintype "passive"))
      (node (ref "R5") (pin "1") (pinfunction "1_1") (pintype "passive"))
    )
    (net (code "21") (name "IO2") (class "Default")
      (node (ref "IC2") (pin "32") (pinfunction "PD2(INT0)_32") (pintype "bidirectional"))
      (node (ref "JP5") (pin "3") (pinfunction "3_3") (pintype "passive"))
    )
    (net (code "22") (name "IO3") (class "Default")
      (node (ref "IC2") (pin "1") (pinfunction "PD3(INT1)_1") (pintype "bidirectional"))
      (node (ref "JP5") (pin "4") (pinfunction "4_4") (pintype "passive"))
    )
    (net (code "23") (name "IO4") (class "Default")
      (node (ref "IC2") (pin "2") (pinfunction "PD4(XCK/T0)_2") (pintype "bidirectional"))
      (node (ref "JP5") (pin "5") (pinfunction "5_5") (pintype "passive"))
    )
    (net (code "24") (name "IO5") (class "Default")
      (node (ref "IC2") (pin "9") (pinfunction "PD5(T1)_9") (pintype "bidirectional"))
      (node (ref "JP5") (pin "6") (pinfunction "6_6") (pintype "passive"))
    )
    (net (code "25") (name "IO6") (class "Default")
      (node (ref "IC2") (pin "10") (pinfunction "PD6(AIN0)_10") (pintype "bidirectional"))
      (node (ref "JP5") (pin "7") (pinfunction "7_7") (pintype "passive"))
    )
    (net (code "26") (name "IO9") (class "Default")
      (node (ref "IC2") (pin "13") (pinfunction "PB1(OC1A)_13") (pintype "bidirectional"))
      (node (ref "JP3") (pin "2") (pinfunction "2_2") (pintype "passive"))
    )
    (net (code "27") (name "M8RXD") (class "Default")
      (node (ref "IC3") (pin "1") (pinfunction "TXD_1") (pintype "output"))
      (node (ref "R4") (pin "2") (pinfunction "2_2") (pintype "passive"))
    )
    (net (code "28") (name "M8TXD") (class "Default")
      (node (ref "IC3") (pin "5") (pinfunction "RXD_5") (pintype "input"))
      (node (ref "R5") (pin "2") (pinfunction "2_2") (pintype "passive"))
    )
    (net (code "29") (name "MISO") (class "Default")
      (node (ref "IC2") (pin "16") (pinfunction "PB4(MISO)_16") (pintype "bidirectional"))
      (node (ref "JP2") (pin "1") (pinfunction "1_1") (pintype "passive"))
      (node (ref "JP3") (pin "5") (pinfunction "5_5") (pintype "passive"))
    )
    (net (code "30") (name "MOSI") (class "Default")
      (node (ref "IC2") (pin "15") (pinfunction "PB3(MOSI/OC2)_15") (pintype "bidirectional"))
      (node (ref "JP2") (pin "4") (pinfunction "4_4") (pintype "passive"))
      (node (ref "JP3") (pin "4") (pinfunction "4_4") (pintype "passive"))
      (node (ref "SJ3") (pin "1") (pinfunction "1_1") (pintype "passive"))
    )
    (net (code "31") (name "NETLIGHT") (class "Default")
      (node (ref "R22") (pin "1") (pinfunction "1_1") (pintype "passive"))
      (node (ref "U3") (pin "52") (pinfunction "NETLIGHT_52") (pintype "power_in"))
    )
    (net (code "32") (name "Net-(C23-Pad1)") (class "Default")
      (node (ref "C23") (pin "1") (pinfunction "1_1") (pintype "passive"))
      (node (ref "GPS_ANT") (pin "D") (pinfunction "D_D") (pintype "bidirectional"))
      (node (ref "L6") (pin "1") (pinfunction "1_1") (pintype "passive"))
    )
    (net (code "33") (name "Net-(C32-Pad2)") (class "Default")
      (node (ref "C32") (pin "2") (pinfunction "2_2") (pintype "passive"))
      (node (ref "L6") (pin "2") (pinfunction "2_2") (pintype "passive"))
      (node (ref "R31") (pin "1") (pinfunction "1_1") (pintype "passive"))
    )
    (net (code "34") (name "Net-(D5-Pad-)") (class "Default")
      (node (ref "D5") (pin "-") (pinfunction "-_-") (pintype "passive"))
      (node (ref "R26") (pin "1") (pinfunction "1_1") (pintype "passive"))
    )
    (net (code "35") (name "Net-(D6-Pad-)") (class "Default")
      (node (ref "D6") (pin "-") (pinfunction "-_-") (pintype "passive"))
      (node (ref "R25") (pin "1") (pinfunction "1_1") (pintype "passive"))
    )
    (net (code "36") (name "Net-(IC2-PB6(XTAL1{slash}TOSC1))") (class "Default")
      (node (ref "C4") (pin "2") (pinfunction "2_2") (pintype "passive"))
      (node (ref "IC2") (pin "7") (pinfunction "PB6(XTAL1/TOSC1)_7") (pintype "bidirectional"))
      (node (ref "Q6") (pin "1") (pinfunction "1_1") (pintype "passive"))
      (node (ref "R2") (pin "1") (pinfunction "1_1") (pintype "passive"))
    )
    (net (code "37") (name "Net-(IC2-PB7(XTAL2{slash}TOSC2))") (class "Default")
      (node (ref "C3") (pin "2") (pinfunction "2_2") (pintype "passive"))
      (node (ref "IC2") (pin "8") (pinfunction "PB7(XTAL2/TOSC2)_8") (pintype "bidirectional"))
      (node (ref "Q6") (pin "3") (pinfunction "2_3") (pintype "passive"))
      (node (ref "R2") (pin "2") (pinfunction "2_2") (pintype "passive"))
    )
    (net (code "38") (name "Net-(IC3-3V3OUT)") (class "Default")
      (node (ref "C9") (pin "1") (pinfunction "1_1") (pintype "passive"))
      (node (ref "IC3") (pin "17") (pinfunction "3V3OUT_17") (pintype "output"))
    )
    (net (code "39") (name "Net-(L4-Pad2)") (class "Default")
      (node (ref "L4") (pin "2") (pinfunction "2_2") (pintype "passive"))
      (node (ref "X2") (pin "VBUS") (pinfunction "VBUS_VBUS") (pintype "power_in"))
    )
    (net (code "40") (name "Net-(LED-PadA)") (class "Default")
      (node (ref "LED") (pin "A") (pinfunction "A_A") (pintype "passive"))
      (node (ref "R7") (pin "1") (pinfunction "1_1") (pintype "passive"))
    )
    (net (code "41") (name "Net-(LED1-PadA)") (class "Default")
      (node (ref "LED1") (pin "A") (pinfunction "A_A") (pintype "passive"))
      (node (ref "R6") (pin "1") (pinfunction "1_1") (pintype "passive"))
    )
    (net (code "42") (name "Net-(Q2-B)") (class "Default")
      (node (ref "Q2") (pin "1") (pinfunction "B_1") (pintype "passive"))
      (node (ref "R19") (pin "2") (pinfunction "2_2") (pintype "passive"))
      (node (ref "R20") (pin "1") (pinfunction "1_1") (pintype "passive"))
    )
    (net (code "43") (name "Net-(Q3-B)") (class "Default")
      (node (ref "Q3") (pin "1") (pinfunction "B_1") (pintype "passive"))
      (node (ref "R21") (pin "2") (pinfunction "2_2") (pintype "passive"))
      (node (ref "R23") (pin "1") (pinfunction "1_1") (pintype "passive"))
    )
    (net (code "44") (name "Net-(Q3-C)") (class "Default")
      (node (ref "Q3") (pin "3") (pinfunction "C_3") (pintype "passive"))
      (node (ref "R25") (pin "2") (pinfunction "2_2") (pintype "passive"))
    )
    (net (code "45") (name "Net-(Q4-B)") (class "Default")
      (node (ref "Q4") (pin "1") (pinfunction "B_1") (pintype "passive"))
      (node (ref "R22") (pin "2") (pinfunction "2_2") (pintype "passive"))
      (node (ref "R24") (pin "1") (pinfunction "1_1") (pintype "passive"))
    )
    (net (code "46") (name "Net-(Q4-C)") (class "Default")
      (node (ref "Q4") (pin "3") (pinfunction "C_3") (pintype "passive"))
      (node (ref "R26") (pin "2") (pinfunction "2_2") (pintype "passive"))
    )
    (net (code "47") (name "Net-(Q5-B)") (class "Default")
      (node (ref "Q5") (pin "1") (pinfunction "B_1") (pintype "passive"))
      (node (ref "R27") (pin "2") (pinfunction "2_2") (pintype "passive"))
      (node (ref "R28") (pin "1") (pinfunction "1_1") (pintype "passive"))
    )
    (net (code "48") (name "Net-(R8-Pad1)") (class "Default")
      (node (ref "R8") (pin "1") (pinfunction "1_1") (pintype "passive"))
      (node (ref "TX") (pin "A") (pinfunction "A_A") (pintype "passive"))
    )
    (net (code "49") (name "Net-(R9-Pad1)") (class "Default")
      (node (ref "R9") (pin "1") (pinfunction "1_1") (pintype "passive"))
      (node (ref "RX") (pin "A") (pinfunction "A_A") (pintype "passive"))
    )
    (net (code "50") (name "Net-(T1-S)") (class "Default")
      (node (ref "D2") (pin "A") (pinfunction "A_A") (pintype "passive"))
      (node (ref "T1") (pin "2") (pinfunction "S_2") (pintype "passive"))
    )
    (net (code "51") (name "Net-(U1-ADJ)") (class "Default")
      (node (ref "R13") (pin "2") (pinfunction "2_2") (pintype "passive"))
      (node (ref "R14") (pin "1") (pinfunction "1_1") (pintype "passive"))
      (node (ref "U1") (pin "5") (pinfunction "ADJ_5") (pintype "bidirectional"))
    )
    (net (code "52") (name "Net-(U1-OUT)") (class "Default")
      (node (ref "C18") (pin "+") (pinfunction "+_+") (pintype "passive"))
      (node (ref "C20") (pin "2") (pinfunction "2_2") (pintype "passive"))
      (node (ref "L3") (pin "2") (pinfunction "2_2") (pintype "passive"))
      (node (ref "R14") (pin "2") (pinfunction "2_2") (pintype "passive"))
      (node (ref "R15") (pin "2") (pinfunction "2_2") (pintype "passive"))
      (node (ref "U1") (pin "4") (pinfunction "OUT_4") (pintype "bidirectional"))
    )
    (net (code "53") (name "Net-(U2-CLK)") (class "Default")
      (node (ref "R17") (pin "1") (pinfunction "1_1") (pintype "passive"))
      (node (ref "U2") (pin "3") (pinfunction "CLK_3") (pintype "bidirectional"))
    )
    (net (code "54") (name "Net-(U2-I{slash}O)") (class "Default")
      (node (ref "R18") (pin "2") (pinfunction "2_2") (pintype "passive"))
      (node (ref "U2") (pin "7") (pinfunction "I/O_7") (pintype "bidirectional"))
    )
    (net (code "55") (name "Net-(U2-RST)") (class "Default")
      (node (ref "R16") (pin "1") (pinfunction "1_1") (pintype "passive"))
      (node (ref "U2") (pin "2") (pinfunction "RST_2") (pintype "bidirectional"))
    )
    (net (code "56") (name "Net-(U4-A8)") (class "Default")
      (node (ref "R12") (pin "1") (pinfunction "1_1") (pintype "passive"))
      (node (ref "U4") (pin "9") (pinfunction "A8_9") (pintype "bidirectional"))
    )
    (net (code "57") (name "Net-(U4-B8)") (class "Default")
      (node (ref "R29") (pin "1") (pinfunction "1_1") (pintype "passive"))
      (node (ref "U4") (pin "12") (pinfunction "B8_12") (pintype "bidirectional"))
    )
    (net (code "58") (name "PWRIN") (class "Default")
      (node (ref "D1") (pin "A") (pinfunction "A_A") (pintype "passive"))
      (node (ref "R10") (pin "2") (pinfunction "2_2") (pintype "passive"))
      (node (ref "X3") (pin "2") (pinfunction "2_2") (pintype "power_in"))
    )
    (net (code "59") (name "PWRKEY") (class "Default")
      (node (ref "C30") (pin "2") (pinfunction "2_2") (pintype "passive"))
      (node (ref "PWR") (pin "2") (pinfunction "S_2") (pintype "passive"))
      (node (ref "Q2") (pin "3") (pinfunction "C_3") (pintype "passive"))
      (node (ref "U3") (pin "1") (pinfunction "PWRKEY_1") (pintype "input"))
    )
    (net (code "60") (name "RESET") (class "Default")
      (node (ref "C2") (pin "2") (pinfunction "2_2") (pintype "passive"))
      (node (ref "IC2") (pin "29") (pinfunction "PC6(/RESET)_29") (pintype "bidirectional"))
      (node (ref "JP1") (pin "1") (pinfunction "1_1") (pintype "passive"))
      (node (ref "JP2") (pin "5") (pinfunction "5_5") (pintype "passive"))
      (node (ref "R3") (pin "1") (pinfunction "1_1") (pintype "passive"))
      (node (ref "RESET") (pin "1") (pinfunction "P_1") (pintype "passive"))
      (node (ref "SJ1") (pin "1") (pinfunction "1_1") (pintype "passive"))
      (node (ref "SJ1") (pin "2") (pinfunction "2_2") (pintype "passive"))
    )
    (net (code "61") (name "RF_ANT") (class "Default")
      (node (ref "RF_ANT") (pin "D") (pinfunction "D_D") (pintype "bidirectional"))
      (node (ref "U3") (pin "60") (pinfunction "RF_ANT_60") (pintype "power_in"))
    )
    (net (code "62") (name "RXLED") (class "Default")
      (node (ref "IC3") (pin "22") (pinfunction "RXLED_22") (pintype "input"))
      (node (ref "RX") (pin "C") (pinfunction "C_C") (pintype "passive"))
    )
    (net (code "63") (name "SCK") (class "Default")
      (node (ref "IC2") (pin "17") (pinfunction "PB5(SCK)_17") (pintype "bidirectional"))
      (node (ref "JP2") (pin "3") (pinfunction "3_3") (pintype "passive"))
      (node (ref "JP3") (pin "6") (pinfunction "6_6") (pintype "passive"))
      (node (ref "R7") (pin "2") (pinfunction "2_2") (pintype "passive"))
      (node (ref "SJ2") (pin "1") (pinfunction "1_1") (pintype "passive"))
    )
    (net (code "64") (name "SHIELD") (class "Default")
      (node (ref "L5") (pin "2") (pinfunction "2_2") (pintype "passive"))
      (node (ref "X2") (pin "BASE@1") (pinfunction "P$1_BASE@1") (pintype "bidirectional"))
      (node (ref "X2") (pin "BASE@2") (pinfunction "P$1_BASE@2") (pintype "bidirectional"))
      (node (ref "X2") (pin "SPRT@1") (pinfunction "P$1_SPRT@1") (pintype "bidirectional"))
      (node (ref "X2") (pin "SPRT@2") (pinfunction "P$1_SPRT@2") (pintype "bidirectional"))
      (node (ref "X2") (pin "SPRT@3") (pinfunction "P$1_SPRT@3") (pintype "bidirectional"))
      (node (ref "X2") (pin "SPRT@4") (pinfunction "P$1_SPRT@4") (pintype "bidirectional"))
    )
    (net (code "65") (name "SIM7000_PWRKEY_MCU") (class "Default")
      (node (ref "R19") (pin "1") (pinfunction "1_1") (pintype "passive"))
      (node (ref "SJ2") (pin "2") (pinfunction "2_2") (pintype "passive"))
    )
    (net (code "66") (name "SIM7000_RESET") (class "Default")
      (node (ref "C29") (pin "2") (pinfunction "2_2") (pintype "passive"))
      (node (ref "Q5") (pin "3") (pinfunction "C_3") (pintype "passive"))
      (node (ref "RST") (pin "2") (pinfunction "S_2") (pintype "passive"))
      (node (ref "U3") (pin "16") (pinfunction "NRESET_16") (pintype "input"))
    )
    (net (code "67") (name "SIM7000_RESET_MCU") (class "Default")
      (node (ref "R27") (pin "1") (pinfunction "1_1") (pintype "passive"))
      (node (ref "SJ3") (pin "2") (pinfunction "2_2") (pintype "passive"))
    )
    (net (code "68") (name "SIM7000_RXD") (class "Default")
      (node (ref "U3") (pin "10") (pinfunction "RXD_10") (pintype "input"))
      (node (ref "U4") (pin "3") (pinfunction "A2_3") (pintype "bidirectional"))
    )
    (net (code "69") (name "SIM7000_TXD") (class "Default")
      (node (ref "U3") (pin "9") (pinfunction "TXD_9") (pintype "output"))
      (node (ref "U4") (pin "1") (pinfunction "A1_1") (pintype "bidirectional"))
    )
    (net (code "70") (name "SIM_ADC") (class "Default")
      (node (ref "U3") (pin "25") (pinfunction "ADC_25") (pintype "input"))
    )
    (net (code "71") (name "SIM_CLK") (class "Default")
      (node (ref "C24") (pin "2") (pinfunction "2_2") (pintype "passive"))
      (node (ref "D4") (pin "5") (pinfunction "C4_5") (pintype "passive"))
      (node (ref "R17") (pin "2") (pinfunction "2_2") (pintype "passive"))
      (node (ref "U3") (pin "32") (pinfunction "SIM_CLK_32") (pintype "output"))
    )
    (net (code "72") (name "SIM_DATA") (class "Default")
      (node (ref "C26") (pin "2") (pinfunction "2_2") (pintype "passive"))
      (node (ref "D4") (pin "4") (pinfunction "C3_4") (pintype "passive"))
      (node (ref "R18") (pin "1") (pinfunction "1_1") (pintype "passive"))
      (node (ref "U3") (pin "31") (pinfunction "SIM_DATA_31") (pintype "output"))
    )
    (net (code "73") (name "SIM_GPIO0") (class "Default")
      (node (ref "U3") (pin "50") (pinfunction "GPIO0_50") (pintype "bidirectional"))
    )
    (net (code "74") (name "SIM_GPIO1") (class "Default")
      (node (ref "U3") (pin "49") (pinfunction "GPIO1_49") (pintype "bidirectional"))
    )
    (net (code "75") (name "SIM_GPIO2") (class "Default")
      (node (ref "U3") (pin "67") (pinfunction "GPIO2_67") (pintype "power_in"))
    )
    (net (code "76") (name "SIM_GPIO3") (class "Default")
      (node (ref "U3") (pin "68") (pinfunction "GPIO3_68") (pintype "power_in"))
    )
    (net (code "77") (name "SIM_GPIO4") (class "Default")
      (node (ref "U3") (pin "48") (pinfunction "GPIO4_48") (pintype "input"))
    )
    (net (code "78") (name "SIM_I2C_SCL") (class "Default")
      (node (ref "U3") (pin "38") (pinfunction "SCL_38") (pintype "output"))
    )
    (net (code "79") (name "SIM_I2C_SDA") (class "Default")
      (node (ref "U3") (pin "37") (pinfunction "SDA_37") (pintype "bidirectional"))
    )
    (net (code "80") (name "SIM_RST") (class "Default")
      (node (ref "C25") (pin "2") (pinfunction "2_2") (pintype "passive"))
      (node (ref "D4") (pin "3") (pinfunction "C2_3") (pintype "passive"))
      (node (ref "R16") (pin "2") (pinfunction "2_2") (pintype "passive"))
      (node (ref "U3") (pin "33") (pinfunction "SIM_RST_33") (pintype "bidirectional"))
    )
    (net (code "81") (name "SIM_USB_DM") (class "Default")
      (node (ref "U3") (pin "28") (pinfunction "USB_DM_28") (pintype "output"))
      (node (ref "X2") (pin "D-") (pinfunction "D-_D-") (pintype "bidirectional"))
    )
    (net (code "82") (name "SIM_USB_DP") (class "Default")
      (node (ref "U3") (pin "27") (pinfunction "USB_DP_27") (pintype "bidirectional"))
      (node (ref "X2") (pin "D+") (pinfunction "D+_D+") (pintype "bidirectional"))
    )
    (net (code "83") (name "SIM_VDD") (class "Default")
      (node (ref "C22") (pin "1") (pinfunction "1_1") (pintype "passive"))
      (node (ref "D4") (pin "1") (pinfunction "C1_1") (pintype "passive"))
      (node (ref "U2") (pin "1") (pinfunction "VCC_1") (pintype "bidirectional"))
      (node (ref "U3") (pin "30") (pinfunction "SIM_VDD_30") (pintype "input"))
    )
    (net (code "84") (name "SS") (class "Default")
      (node (ref "IC2") (pin "14") (pinfunction "PB2(SS/OC1B)_14") (pintype "bidirectional"))
      (node (ref "JP3") (pin "3") (pinfunction "3_3") (pintype "passive"))
    )
    (net (code "85") (name "STATUS") (class "Default")
      (node (ref "R21") (pin "1") (pinfunction "1_1") (pintype "passive"))
      (node (ref "U3") (pin "66") (pinfunction "STATUS_66") (pintype "power_in"))
    )
    (net (code "86") (name "TXLED") (class "Default")
      (node (ref "IC3") (pin "23") (pinfunction "TXLED_23") (pintype "input"))
      (node (ref "TX") (pin "C") (pinfunction "C_C") (pintype "passive"))
    )
    (net (code "87") (name "USHIELD") (class "Default")
      (node (ref "C31") (pin "2") (pinfunction "2_2") (pintype "passive"))
      (node (ref "L1") (pin "2") (pinfunction "2_2") (pintype "passive"))
      (node (ref "R30") (pin "1") (pinfunction "1_1") (pintype "passive"))
      (node (ref "X1") (pin "P$1") (pinfunction "P$1_P$1") (pintype "bidirectional"))
      (node (ref "X1") (pin "P$2") (pinfunction "P$2_P$2") (pintype "bidirectional"))
    )
    (net (code "88") (name "V+") (class "Default")
      (node (ref "C34") (pin "1") (pinfunction "1_1") (pintype "passive"))
      (node (ref "C35") (pin "1") (pinfunction "1_1") (pintype "passive"))
      (node (ref "C36") (pin "1") (pinfunction "1_1") (pintype "passive"))
      (node (ref "D5") (pin "+") (pinfunction "+_+") (pintype "passive"))
      (node (ref "D6") (pin "+") (pinfunction "+_+") (pintype "passive"))
      (node (ref "L3") (pin "1") (pinfunction "1_1") (pintype "passive"))
      (node (ref "R31") (pin "2") (pinfunction "2_2") (pintype "passive"))
      (node (ref "U3") (pin "55") (pinfunction "VBAT_55") (pintype "power_in"))
      (node (ref "U3") (pin "56") (pinfunction "VBAT_56") (pintype "power_in"))
      (node (ref "U3") (pin "57") (pinfunction "VBAT_57") (pintype "power_in"))
    )
    (net (code "89") (name "VDD_EXT") (class "Default")
      (node (ref "C27") (pin "2") (pinfunction "2_2") (pintype "passive"))
      (node (ref "U3") (pin "15") (pinfunction "VDD_EXT_15") (pintype "output"))
      (node (ref "U4") (pin "10") (pinfunction "OE_10") (pintype "bidirectional"))
      (node (ref "U4") (pin "2") (pinfunction "VCCA_2") (pintype "bidirectional"))
    )
    (net (code "90") (name "VIN") (class "Default")
      (node (ref "C11") (pin "1") (pinfunction "1_1") (pintype "passive"))
      (node (ref "C13") (pin "2") (pinfunction "2_2") (pintype "passive"))
      (node (ref "C14") (pin "2") (pinfunction "2_2") (pintype "passive"))
      (node (ref "C16") (pin "+") (pinfunction "+_+") (pintype "passive"))
      (node (ref "D1") (pin "C") (pinfunction "C_C") (pintype "passive"))
      (node (ref "D2") (pin "C") (pinfunction "C_C") (pintype "passive"))
      (node (ref "IC4") (pin "3") (pinfunction "IN_3") (pintype "input"))
      (node (ref "JP1") (pin "6") (pinfunction "6_6") (pintype "passive"))
      (node (ref "U1") (pin "1") (pinfunction "EN_1") (pintype "bidirectional"))
      (node (ref "U1") (pin "2") (pinfunction "IN_2") (pintype "bidirectional"))
    )
    (net (code "91") (name "XUSB") (class "Default")
      (node (ref "L2") (pin "2") (pinfunction "2_2") (pintype "passive"))
      (node (ref "X1") (pin "1") (pinfunction "1_1") (pintype "bidirectional"))
    )
    (net (code "92") (name "unconnected-(D4-C5-Pad6)") (class "Default")
      (node (ref "D4") (pin "6") (pinfunction "C5_6") (pintype "passive"))
    )
    (net (code "93") (name "unconnected-(IC1B-OUT-Pad7)") (class "Default")
      (node (ref "IC1") (pin "7") (pinfunction "OUT_7") (pintype "output"))
    )
    (net (code "94") (name "unconnected-(IC2-ADC6-Pad19)") (class "Default")
      (node (ref "IC2") (pin "19") (pinfunction "ADC6_19") (pintype "bidirectional"))
    )
    (net (code "95") (name "unconnected-(IC2-ADC7-Pad22)") (class "Default")
      (node (ref "IC2") (pin "22") (pinfunction "ADC7_22") (pintype "bidirectional"))
    )
    (net (code "96") (name "unconnected-(IC3-CTS-Pad11)") (class "Default")
      (node (ref "IC3") (pin "11") (pinfunction "CTS_11") (pintype "input"))
    )
    (net (code "97") (name "unconnected-(IC3-DCD-Pad10)") (class "Default")
      (node (ref "IC3") (pin "10") (pinfunction "DCD_10") (pintype "input"))
    )
    (net (code "98") (name "unconnected-(IC3-DSR-Pad9)") (class "Default")
      (node (ref "IC3") (pin "9") (pinfunction "DSR_9") (pintype "input"))
    )
    (net (code "99") (name "unconnected-(IC3-OSCI-Pad27)") (class "Default")
      (node (ref "IC3") (pin "27") (pinfunction "OSCI_27") (pintype "input"))
    )
    (net (code "100") (name "unconnected-(IC3-OSCO-Pad28)") (class "Default")
      (node (ref "IC3") (pin "28") (pinfunction "OSCO_28") (pintype "output"))
    )
    (net (code "101") (name "unconnected-(IC3-PWREN-Pad14)") (class "Default")
      (node (ref "IC3") (pin "14") (pinfunction "PWREN_14") (pintype "input"))
    )
    (net (code "102") (name "unconnected-(IC3-RESET-Pad19)") (class "Default")
      (node (ref "IC3") (pin "19") (pinfunction "RESET_19") (pintype "input"))
    )
    (net (code "103") (name "unconnected-(IC3-RI-Pad6)") (class "Default")
      (node (ref "IC3") (pin "6") (pinfunction "RI_6") (pintype "input"))
    )
    (net (code "104") (name "unconnected-(IC3-RTS-Pad3)") (class "Default")
      (node (ref "IC3") (pin "3") (pinfunction "RTS_3") (pintype "output"))
    )
    (net (code "105") (name "unconnected-(IC3-SLEEP-Pad12)") (class "Default")
      (node (ref "IC3") (pin "12") (pinfunction "SLEEP_12") (pintype "input"))
    )
    (net (code "106") (name "unconnected-(IC3-TXDEN-Pad13)") (class "Default")
      (node (ref "IC3") (pin "13") (pinfunction "TXDEN_13") (pintype "input"))
    )
    (net (code "107") (name "unconnected-(U2-VPP-Pad6)") (class "Default")
      (node (ref "U2") (pin "6") (pinfunction "VPP_6") (pintype "bidirectional"))
    )
    (net (code "108") (name "unconnected-(U3-BOOT_CFG-Pad6)") (class "Default")
      (node (ref "U3") (pin "6") (pinfunction "BOOT_CFG_6") (pintype "output"))
    )
    (net (code "109") (name "unconnected-(U3-CTS-Pad7)") (class "Default")
      (node (ref "U3") (pin "7") (pinfunction "CTS_7") (pintype "output"))
    )
    (net (code "110") (name "unconnected-(U3-DCD-Pad5)") (class "Default")
      (node (ref "U3") (pin "5") (pinfunction "DCD_5") (pintype "output"))
    )
    (net (code "111") (name "unconnected-(U3-DTR-Pad3)") (class "Default")
      (node (ref "U3") (pin "3") (pinfunction "DTR_3") (pintype "input"))
    )
    (net (code "112") (name "unconnected-(U3-MDM_LOG_TX-Pad23)") (class "Default")
      (node (ref "U3") (pin "23") (pinfunction "MDM_LOG_TX_23") (pintype "input"))
    )
    (net (code "113") (name "unconnected-(U3-NC-Pad19)") (class "Default")
      (node (ref "U3") (pin "19") (pinfunction "NC_19") (pintype "input"))
    )
    (net (code "114") (name "unconnected-(U3-NC-Pad20)") (class "Default")
      (node (ref "U3") (pin "20") (pinfunction "NC_20") (pintype "output"))
    )
    (net (code "115") (name "unconnected-(U3-NC-Pad21)") (class "Default")
      (node (ref "U3") (pin "21") (pinfunction "NC_21") (pintype "output"))
    )
    (net (code "116") (name "unconnected-(U3-NC-Pad22)") (class "Default")
      (node (ref "U3") (pin "22") (pinfunction "NC_22") (pintype "input"))
    )
    (net (code "117") (name "unconnected-(U3-NC-Pad26)") (class "Default")
      (node (ref "U3") (pin "26") (pinfunction "NC_26") (pintype "output"))
    )
    (net (code "118") (name "unconnected-(U3-NC-Pad35)") (class "Default")
      (node (ref "U3") (pin "35") (pinfunction "NC_35") (pintype "input"))
    )
    (net (code "119") (name "unconnected-(U3-NC-Pad36)") (class "Default")
      (node (ref "U3") (pin "36") (pinfunction "NC_36") (pintype "output"))
    )
    (net (code "120") (name "unconnected-(U3-NC-Pad40)") (class "Default")
      (node (ref "U3") (pin "40") (pinfunction "NC_40") (pintype "output"))
    )
    (net (code "121") (name "unconnected-(U3-NC-Pad41)") (class "Default")
      (node (ref "U3") (pin "41") (pinfunction "NC_41") (pintype "output"))
    )
    (net (code "122") (name "unconnected-(U3-NC-Pad42)") (class "Default")
      (node (ref "U3") (pin "42") (pinfunction "NC_42") (pintype "output"))
    )
    (net (code "123") (name "unconnected-(U3-NC-Pad43)") (class "Default")
      (node (ref "U3") (pin "43") (pinfunction "NC_43") (pintype "output"))
    )
    (net (code "124") (name "unconnected-(U3-NC-Pad44)") (class "Default")
      (node (ref "U3") (pin "44") (pinfunction "NC_44") (pintype "output"))
    )
    (net (code "125") (name "unconnected-(U3-NC-Pad47)") (class "Default")
      (node (ref "U3") (pin "47") (pinfunction "NC_47") (pintype "input"))
    )
    (net (code "126") (name "unconnected-(U3-NC-Pad51)") (class "Default")
      (node (ref "U3") (pin "51") (pinfunction "NC_51") (pintype "bidirectional"))
    )
    (net (code "127") (name "unconnected-(U3-PCM_CLK-Pad11)") (class "Default")
      (node (ref "U3") (pin "11") (pinfunction "PCM_CLK_11") (pintype "output"))
    )
    (net (code "128") (name "unconnected-(U3-PCM_DIN-Pad13)") (class "Default")
      (node (ref "U3") (pin "13") (pinfunction "PCM_DIN_13") (pintype "output"))
    )
    (net (code "129") (name "unconnected-(U3-PCM_DOUT-Pad14)") (class "Default")
      (node (ref "U3") (pin "14") (pinfunction "PCM_DOUT_14") (pintype "output"))
    )
    (net (code "130") (name "unconnected-(U3-PCM_SYNC-Pad12)") (class "Default")
      (node (ref "U3") (pin "12") (pinfunction "PCM_SYNC_12") (pintype "bidirectional"))
    )
    (net (code "131") (name "unconnected-(U3-RI-Pad4)") (class "Default")
      (node (ref "U3") (pin "4") (pinfunction "RI_4") (pintype "output"))
    )
    (net (code "132") (name "unconnected-(U3-RTS-Pad8)") (class "Default")
      (node (ref "U3") (pin "8") (pinfunction "RTS_8") (pintype "input"))
    )
    (net (code "133") (name "unconnected-(U3-SIM_DET-Pad34)") (class "Default")
      (node (ref "U3") (pin "34") (pinfunction "SIM_DET_34") (pintype "bidirectional"))
    )
    (net (code "134") (name "unconnected-(U4-A3-Pad4)") (class "Default")
      (node (ref "U4") (pin "4") (pinfunction "A3_4") (pintype "bidirectional"))
    )
    (net (code "135") (name "unconnected-(U4-A4-Pad5)") (class "Default")
      (node (ref "U4") (pin "5") (pinfunction "A4_5") (pintype "bidirectional"))
    )
    (net (code "136") (name "unconnected-(U4-A5-Pad6)") (class "Default")
      (node (ref "U4") (pin "6") (pinfunction "A5_6") (pintype "bidirectional"))
    )
    (net (code "137") (name "unconnected-(U4-A6-Pad7)") (class "Default")
      (node (ref "U4") (pin "7") (pinfunction "A6_7") (pintype "bidirectional"))
    )
    (net (code "138") (name "unconnected-(U4-A7-Pad8)") (class "Default")
      (node (ref "U4") (pin "8") (pinfunction "A7_8") (pintype "bidirectional"))
    )
    (net (code "139") (name "unconnected-(U4-B3-Pad17)") (class "Default")
      (node (ref "U4") (pin "17") (pinfunction "B3_17") (pintype "bidirectional"))
    )
    (net (code "140") (name "unconnected-(U4-B4-Pad16)") (class "Default")
      (node (ref "U4") (pin "16") (pinfunction "B4_16") (pintype "bidirectional"))
    )
    (net (code "141") (name "unconnected-(U4-B5-Pad15)") (class "Default")
      (node (ref "U4") (pin "15") (pinfunction "B5_15") (pintype "bidirectional"))
    )
    (net (code "142") (name "unconnected-(U4-B6-Pad14)") (class "Default")
      (node (ref "U4") (pin "14") (pinfunction "B6_14") (pintype "bidirectional"))
    )
    (net (code "143") (name "unconnected-(U4-B7-Pad13)") (class "Default")
      (node (ref "U4") (pin "13") (pinfunction "B7_13") (pintype "bidirectional"))
    )
    (net (code "144") (name "unconnected-(X2-PadID)") (class "Default")
      (node (ref "X2") (pin "ID") (pinfunction "ID_ID") (pintype "bidirectional"))
    )
  )
)
